# VDA.net
KiCad netlist of a schematic drawn in EAGLE
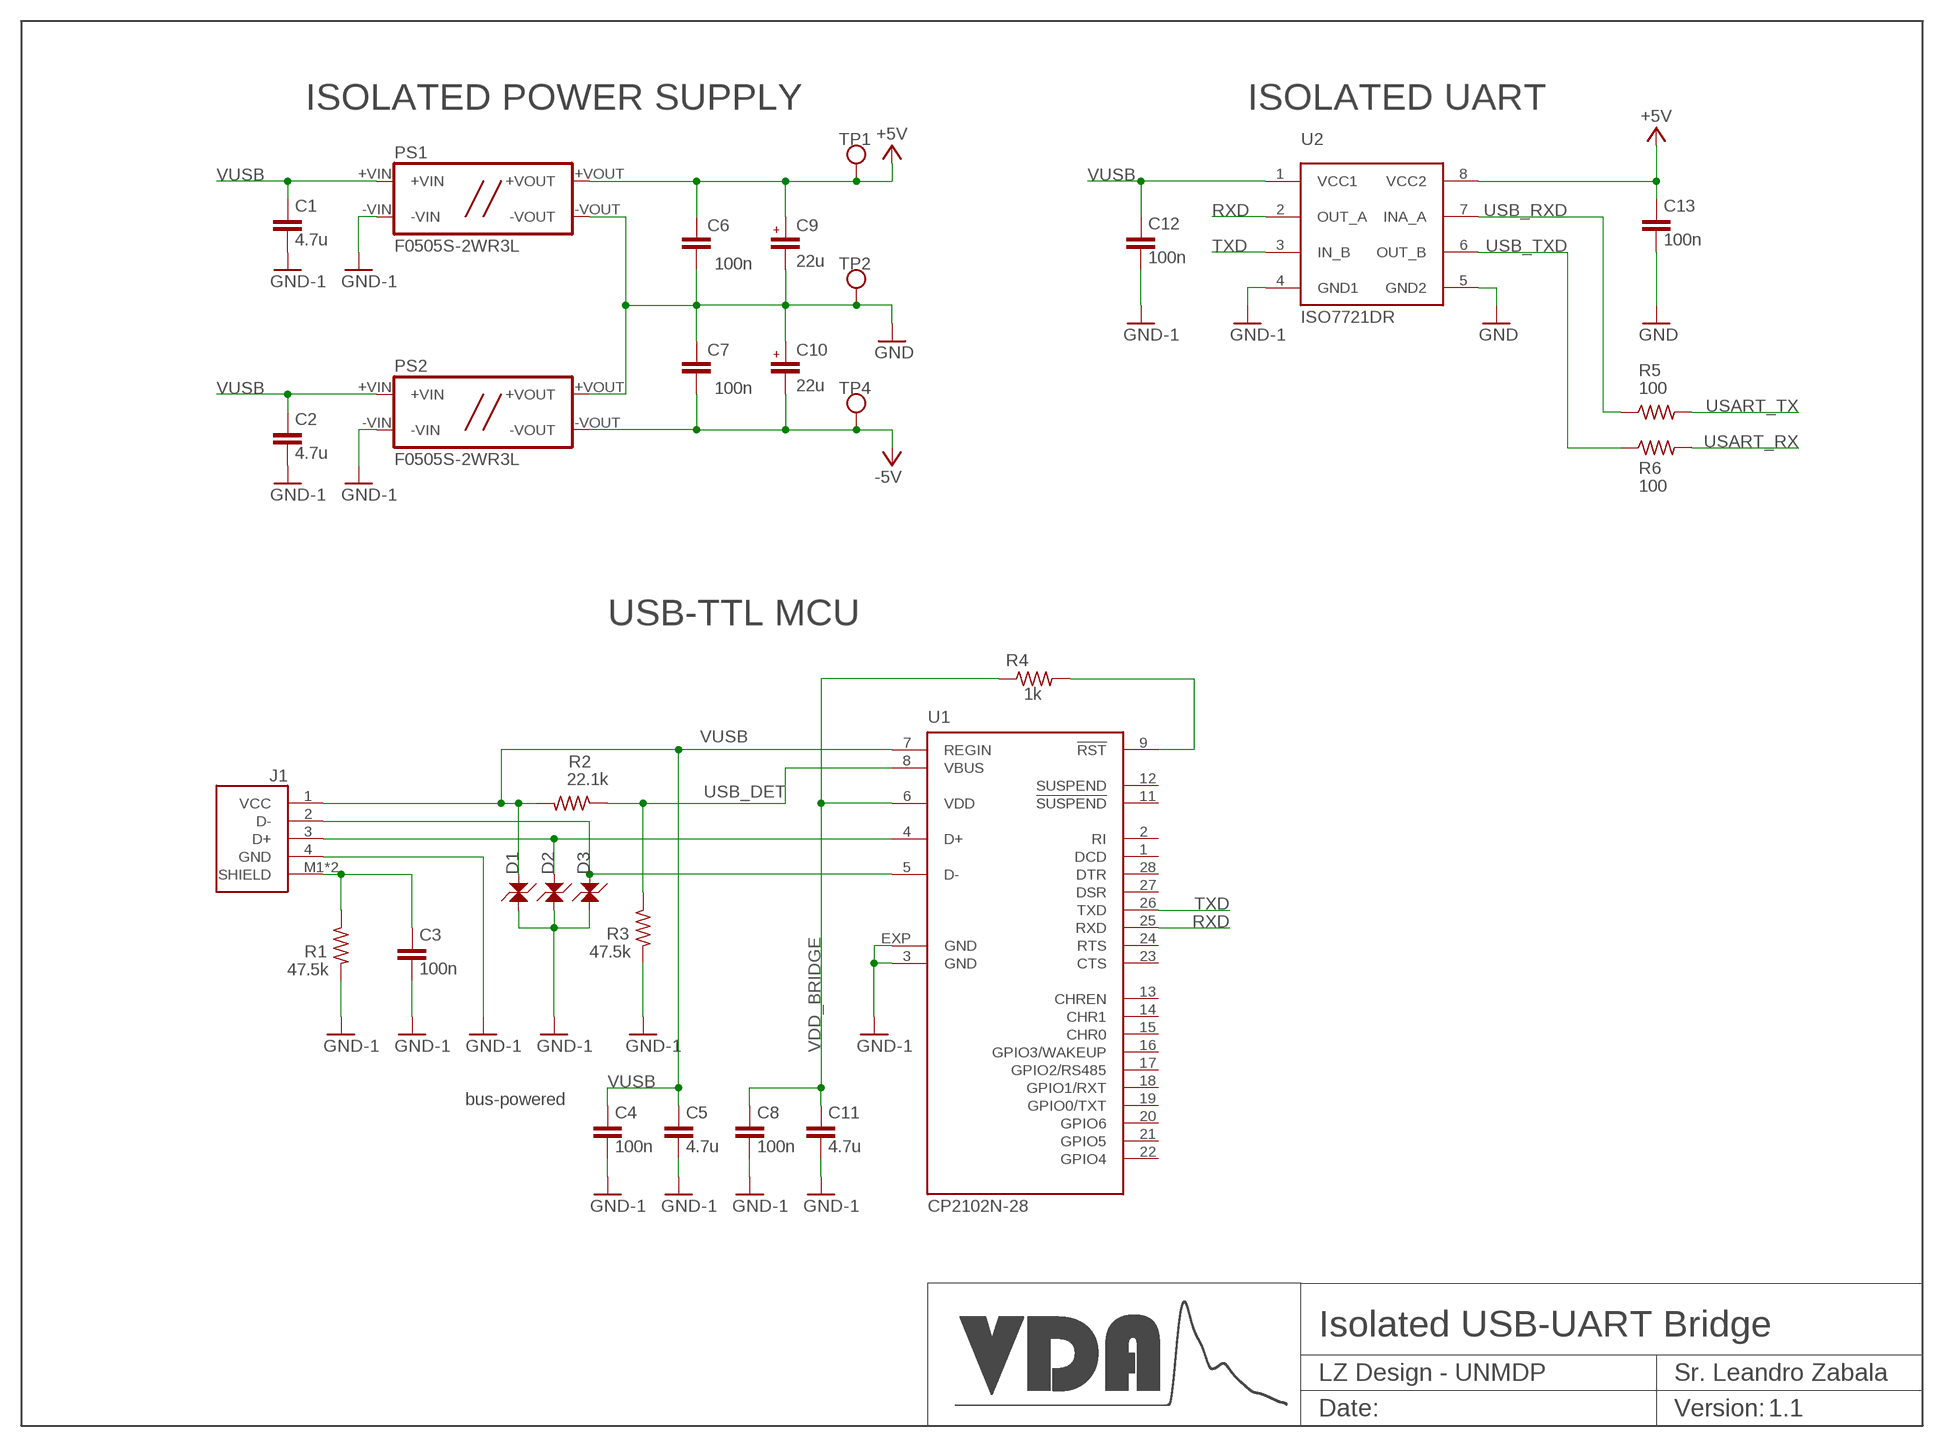
[diagram p0: schematic, sheet 1]
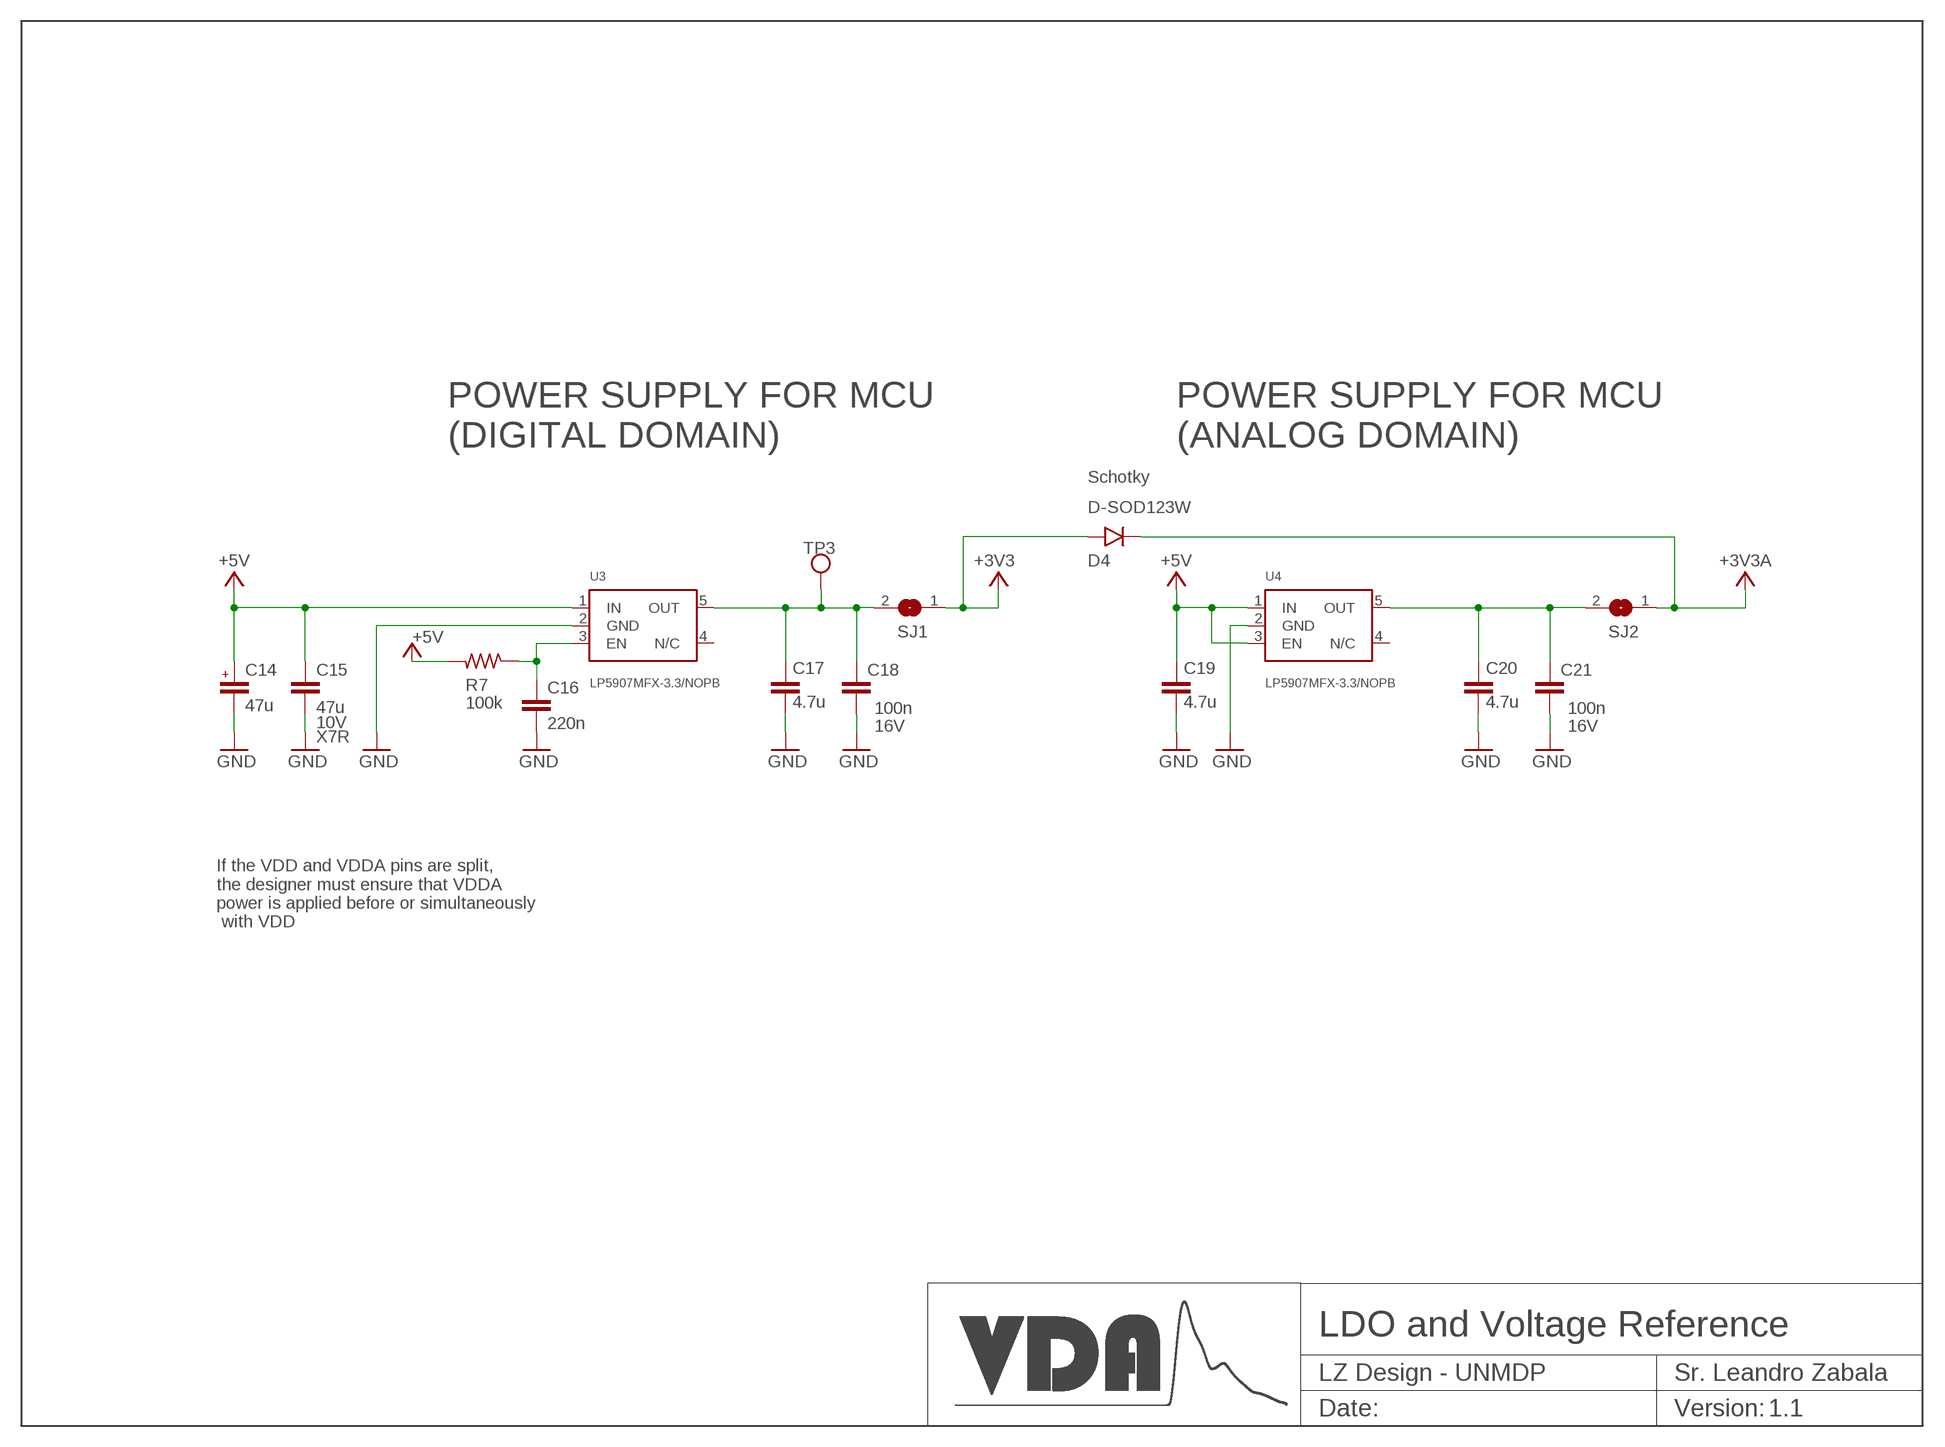
[diagram p1: schematic, sheet 2]
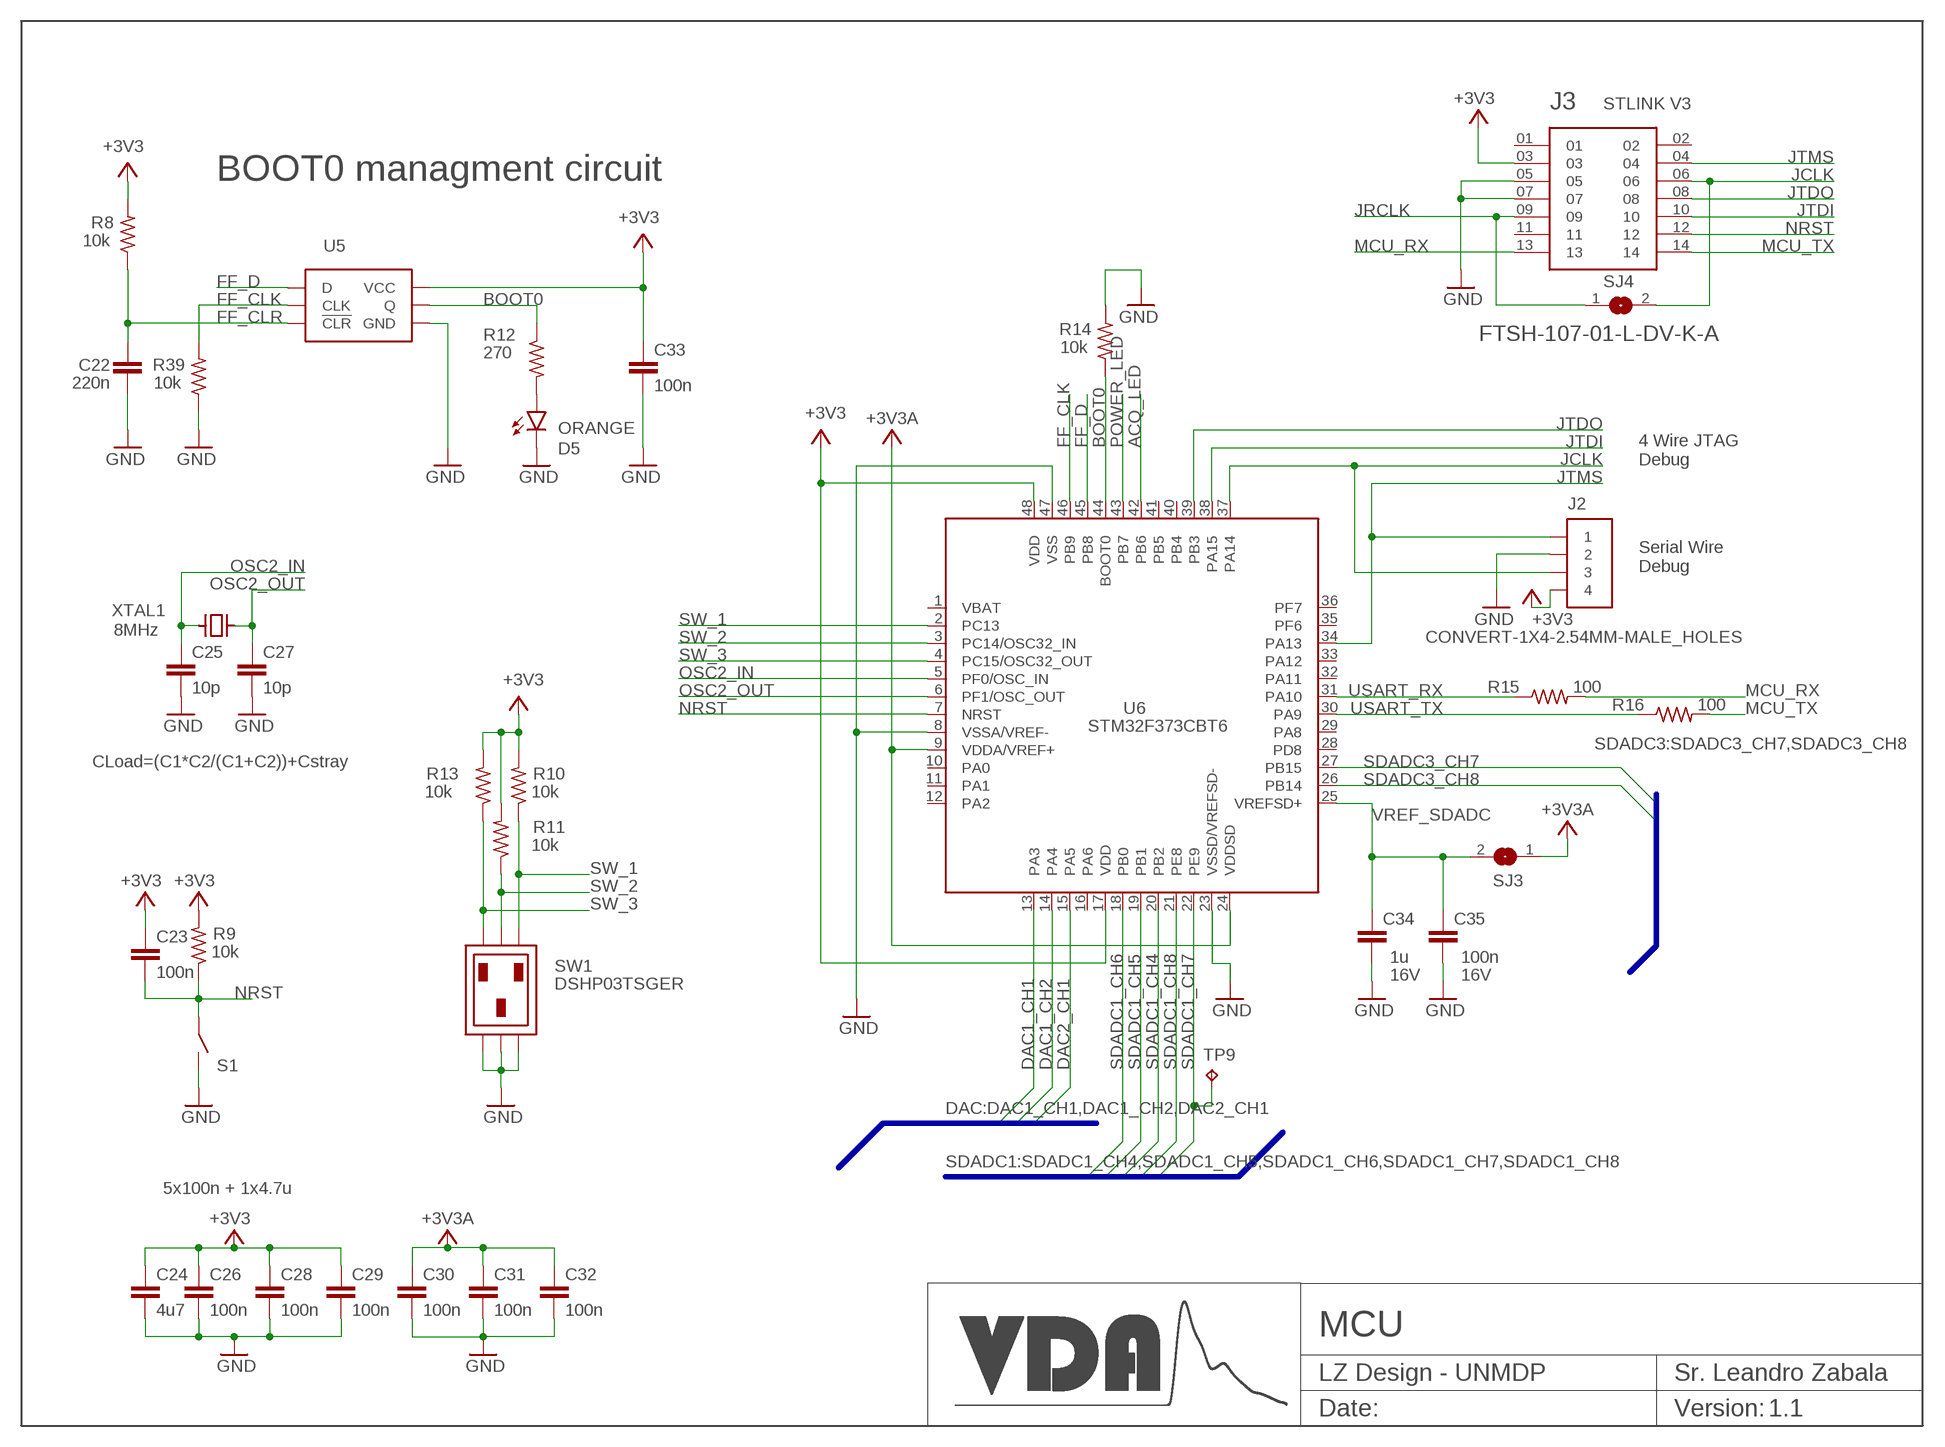
[diagram p2: schematic, sheet 3]
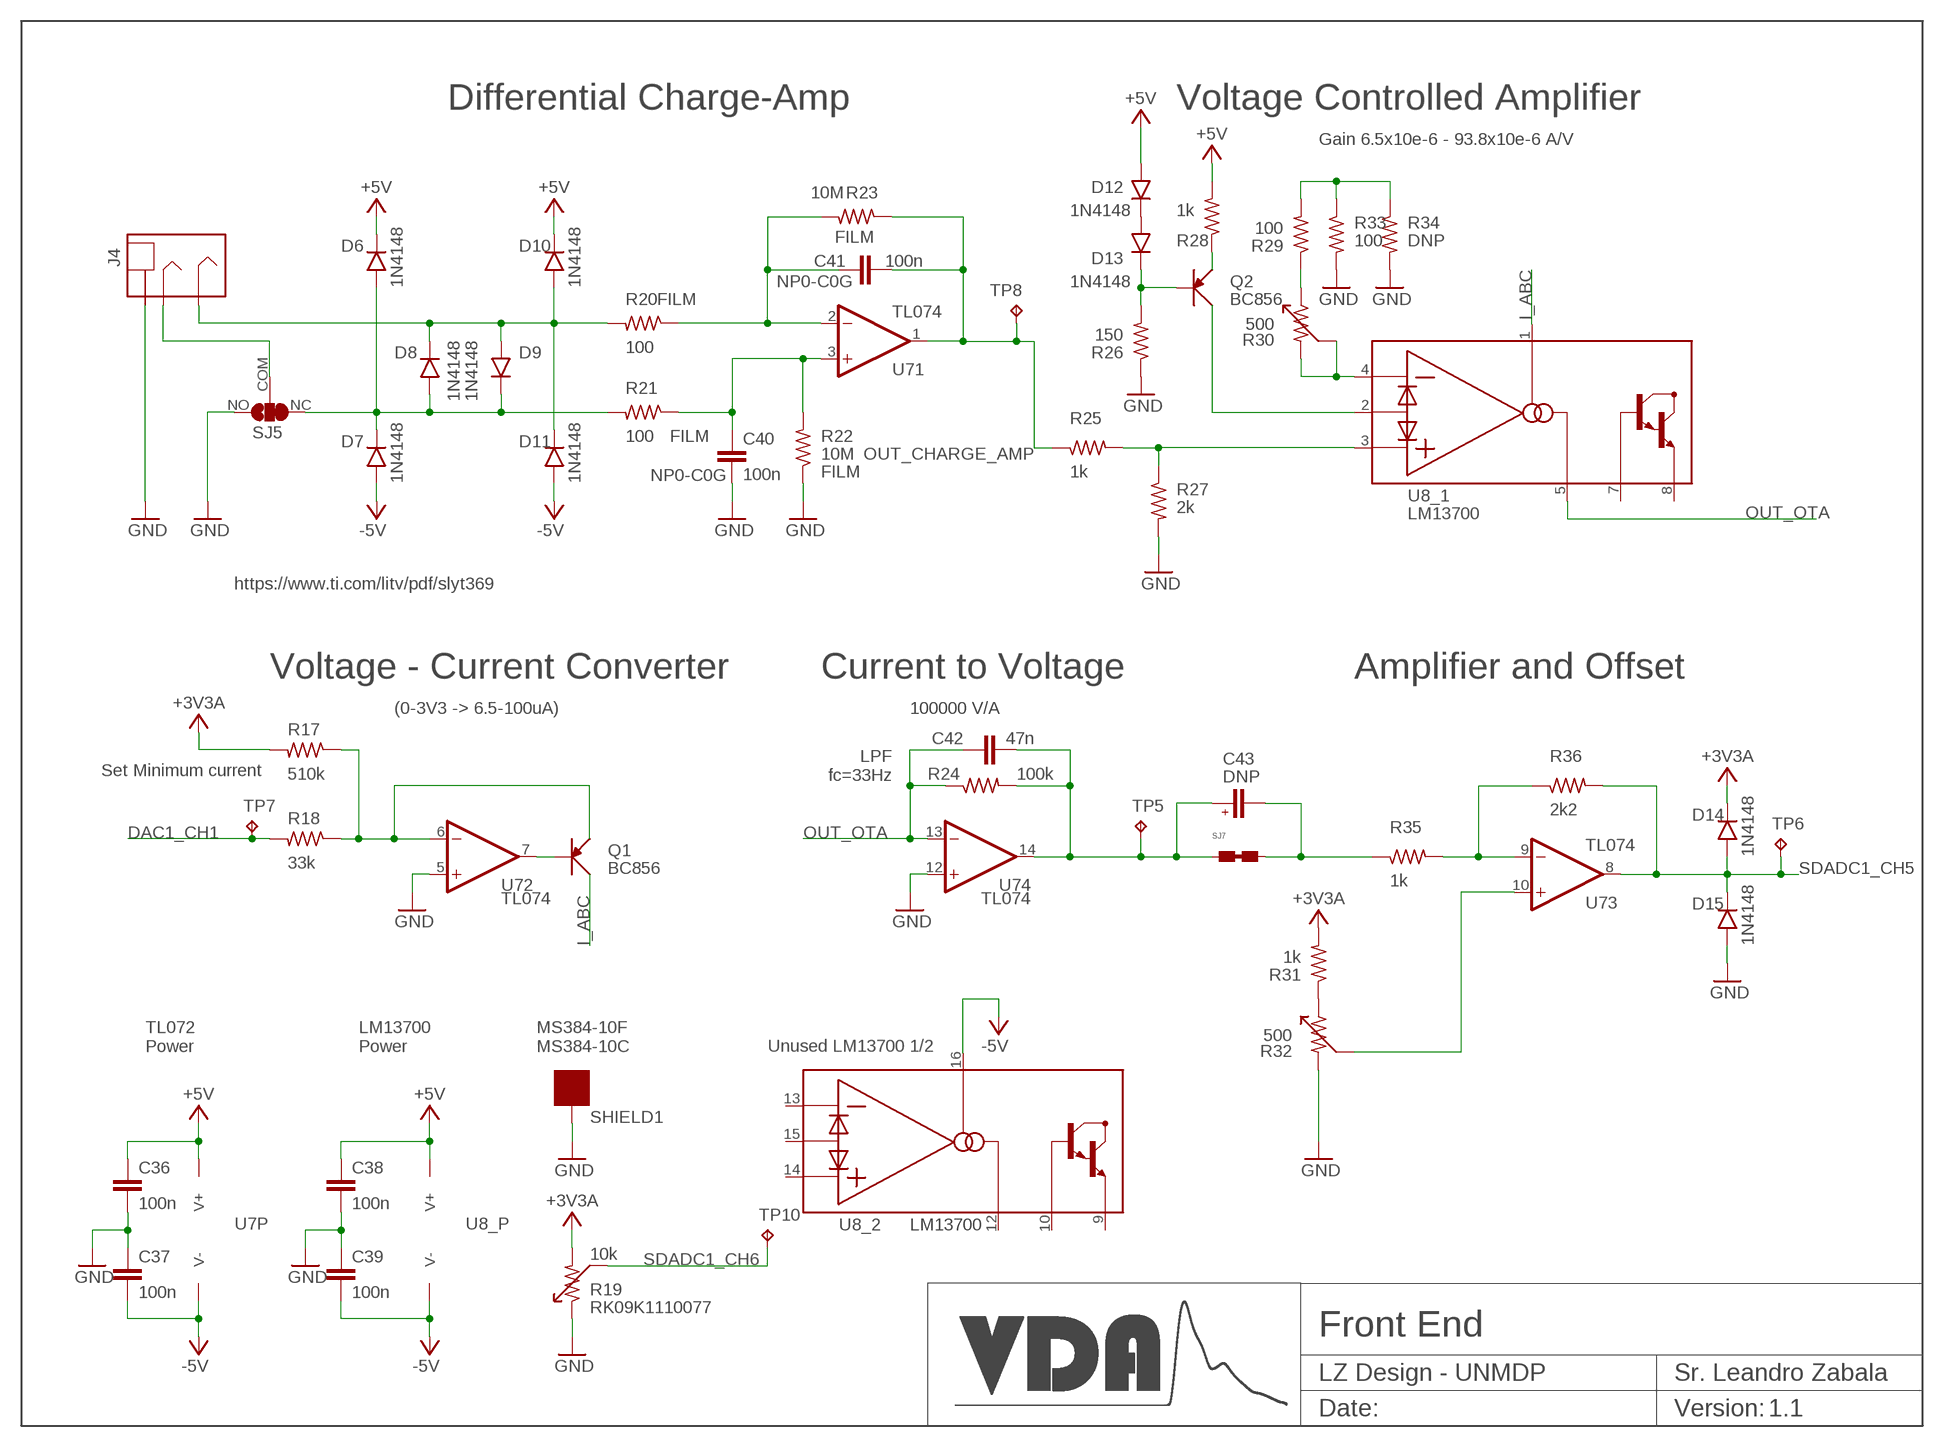
[diagram p3: schematic, sheet 4]
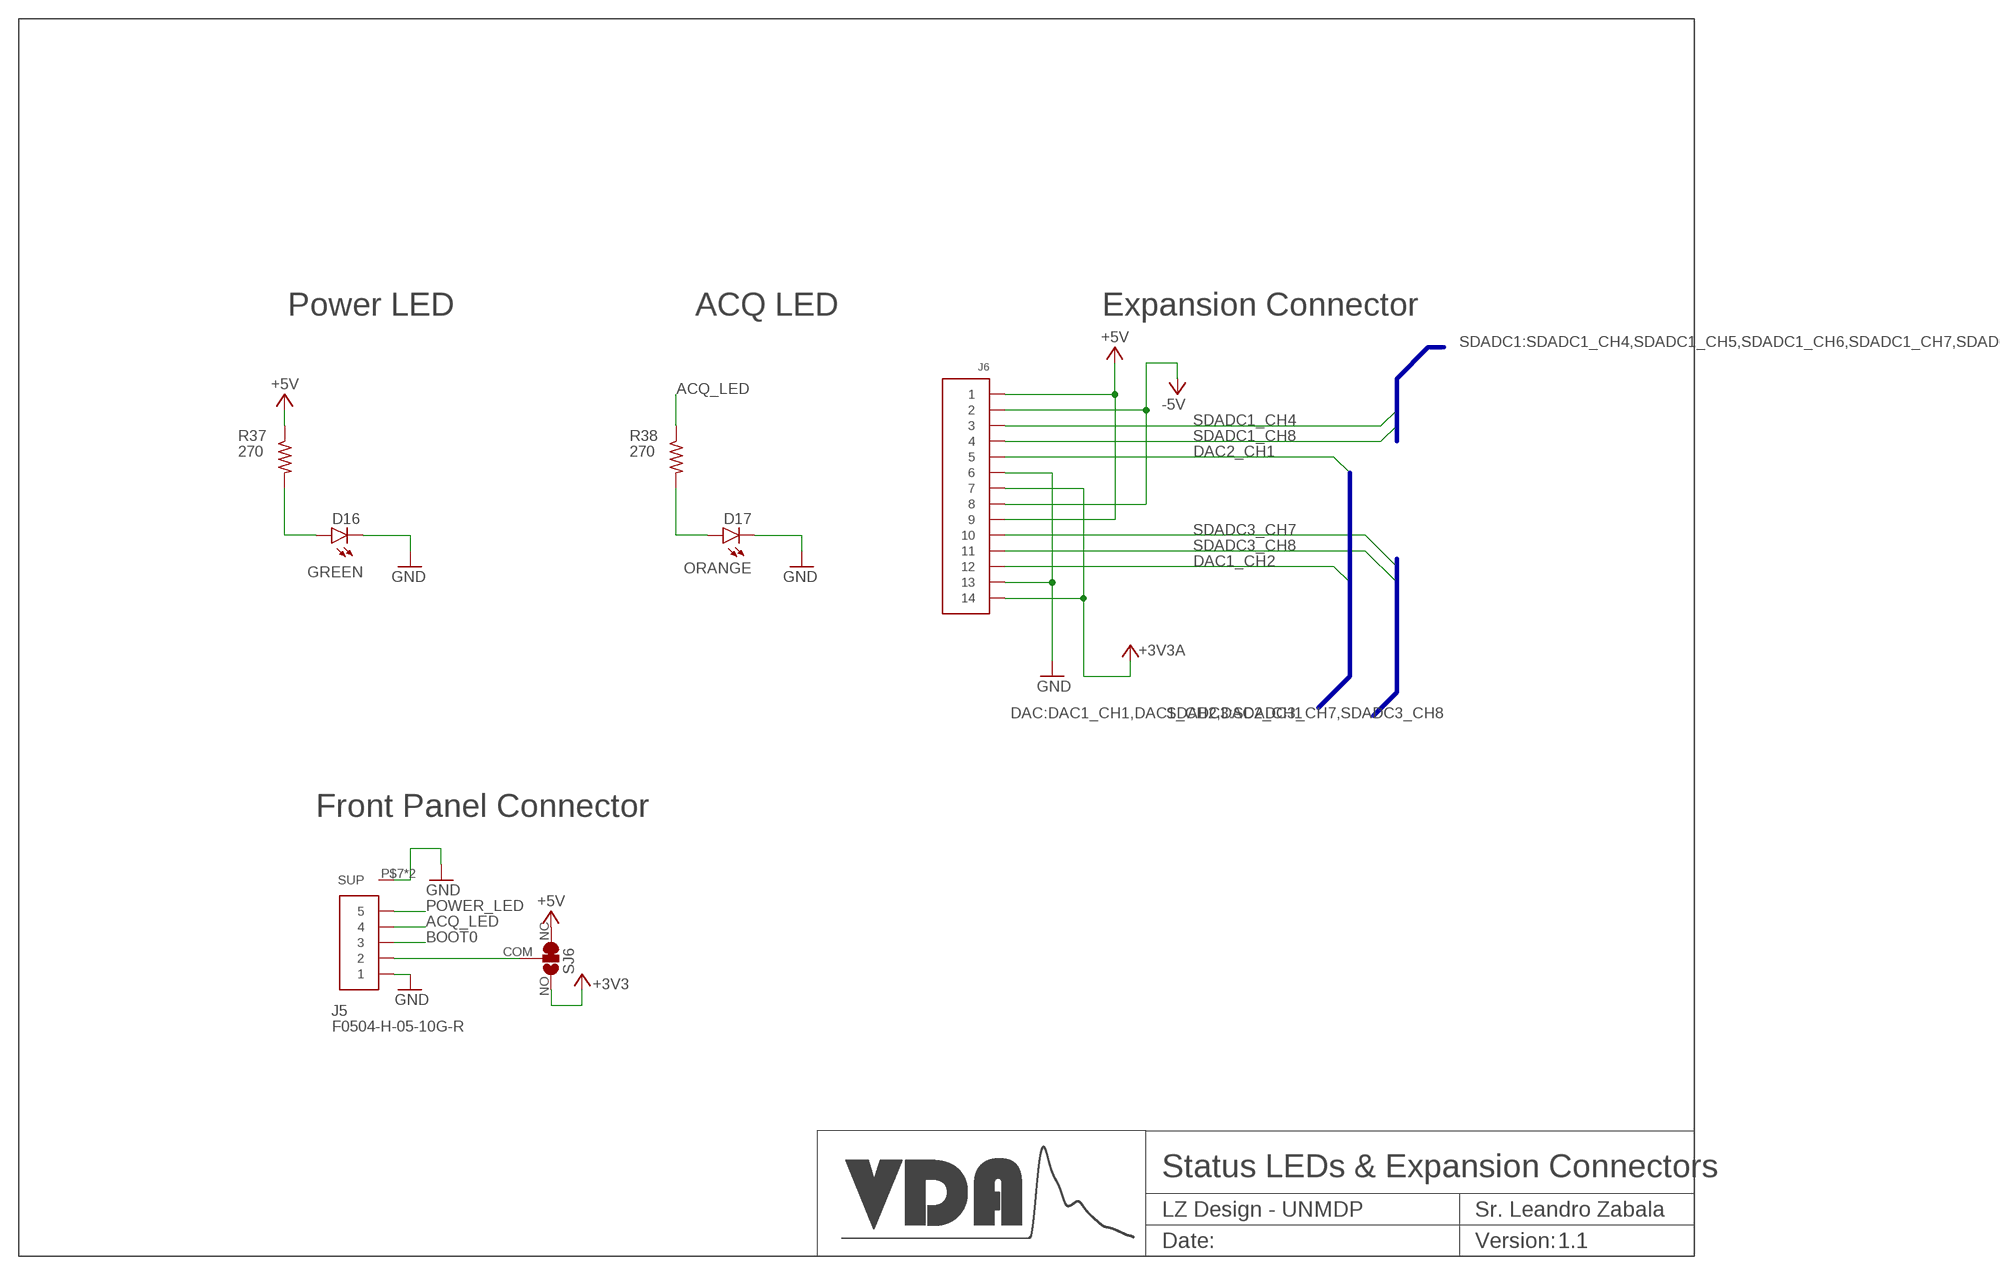
[diagram p4: schematic, sheet 5]

(export (version "E")
  (design (tool "Eeschema 10.0.6"))
  (components
    (comp (ref "C22")
      (value "220n")
      (footprint "eagle-import:C_0603")
      (libsource (lib "eagle-import") (part "C_0603"))
    )
    (comp (ref "C23")
      (value "100n")
      (footprint "eagle-import:C_0603")
      (libsource (lib "eagle-import") (part "C_0603"))
    )
    (comp (ref "C24")
      (value "4u7")
      (footprint "eagle-import:C_0805")
      (libsource (lib "eagle-import") (part "C_0805"))
    )
    (comp (ref "C25")
      (value "10p")
      (footprint "eagle-import:C_0603")
      (libsource (lib "eagle-import") (part "C_0603"))
    )
    (comp (ref "C26")
      (value "100n")
      (footprint "eagle-import:C_0603")
      (libsource (lib "eagle-import") (part "C_0603"))
    )
    (comp (ref "C27")
      (value "10p")
      (footprint "eagle-import:C_0603")
      (libsource (lib "eagle-import") (part "C_0603"))
    )
    (comp (ref "C28")
      (value "100n")
      (footprint "eagle-import:C_0603")
      (libsource (lib "eagle-import") (part "C_0603"))
    )
    (comp (ref "C29")
      (value "100n")
      (footprint "eagle-import:C_0603")
      (libsource (lib "eagle-import") (part "C_0603"))
    )
    (comp (ref "C30")
      (value "100n")
      (footprint "eagle-import:C_0603")
      (libsource (lib "eagle-import") (part "C_0603"))
    )
    (comp (ref "C31")
      (value "100n")
      (footprint "eagle-import:C_0603")
      (libsource (lib "eagle-import") (part "C_0603"))
    )
    (comp (ref "C32")
      (value "100n")
      (footprint "eagle-import:C_0603")
      (libsource (lib "eagle-import") (part "C_0603"))
    )
    (comp (ref "C33")
      (value "100n")
      (footprint "eagle-import:C_0603")
      (libsource (lib "eagle-import") (part "C_0603"))
    )
    (comp (ref "C34")
      (value "1u")
      (footprint "eagle-import:C_0603")
      (fields (field (name "V") "16V"))
      (libsource (lib "eagle-import") (part "C_0603"))
    )
    (comp (ref "C35")
      (value "100n")
      (footprint "eagle-import:C_0603")
      (fields (field (name "V") "16V"))
      (libsource (lib "eagle-import") (part "C_0603"))
    )
    (comp (ref "D5")
      (value "ORANGE")
      (footprint "eagle-import:LED_0603_ARROW")
      (libsource (lib "eagle-import") (part "LED_0603_ARROW"))
    )
    (comp (ref "J2")
      (value "CONVERT-1X4-2.54MM-MALE_HOLES")
      (footprint "eagle-import:1X04")
      (libsource (lib "eagle-import") (part "CONVERT-1X4-2.54MM-MALE_HOLES"))
    )
    (comp (ref "J3")
      (value "FTSH-107-01-L-DV-K-A")
      (footprint "eagle-import:SAMTEC_FTSH-107-01-L-DV-K-A")
      (fields (field (name "MANUFACTURER") "Samtec"))
      (libsource (lib "eagle-import") (part "FTSH-107-01-L-DV-K-A"))
    )
    (comp (ref "R8")
      (value "10k")
      (footprint "eagle-import:R_0603")
      (libsource (lib "eagle-import") (part "R_0603"))
    )
    (comp (ref "R9")
      (value "10k")
      (footprint "eagle-import:R_0603")
      (libsource (lib "eagle-import") (part "R_0603"))
    )
    (comp (ref "R10")
      (value "10k")
      (footprint "eagle-import:R_0603")
      (libsource (lib "eagle-import") (part "R_0603"))
    )
    (comp (ref "R11")
      (value "10k")
      (footprint "eagle-import:R_0603")
      (libsource (lib "eagle-import") (part "R_0603"))
    )
    (comp (ref "R12")
      (value "270")
      (footprint "eagle-import:R_0603")
      (libsource (lib "eagle-import") (part "R_0603"))
    )
    (comp (ref "R13")
      (value "10k")
      (footprint "eagle-import:R_0603")
      (libsource (lib "eagle-import") (part "R_0603"))
    )
    (comp (ref "R14")
      (value "10k")
      (footprint "eagle-import:R_0603")
      (libsource (lib "eagle-import") (part "R_0603"))
    )
    (comp (ref "R15")
      (value "100")
      (footprint "eagle-import:R_0603")
      (libsource (lib "eagle-import") (part "R_0603"))
    )
    (comp (ref "R16")
      (value "100")
      (footprint "eagle-import:R_0603")
      (libsource (lib "eagle-import") (part "R_0603"))
    )
    (comp (ref "R39")
      (value "10k")
      (footprint "eagle-import:R_0603")
      (libsource (lib "eagle-import") (part "R_0603"))
    )
    (comp (ref "S1")
      (value "TSWITCH_SMTR2")
      (footprint "eagle-import:SMTR2")
      (libsource (lib "eagle-import") (part "TSWITCH_SMTR2"))
    )
    (comp (ref "SJ3") (value "SJ") (footprint "eagle-import:SJ") (libsource (lib "eagle-import") (part "SJ")))
    (comp (ref "SJ4") (value "SJ") (footprint "eagle-import:SJ") (libsource (lib "eagle-import") (part "SJ")))
    (comp (ref "SW1")
      (value "DSHP03TSGER")
      (footprint "eagle-import:DIPSW-3")
      (libsource (lib "eagle-import") (part "DIPSW-3"))
    )
    (comp (ref "TP9")
      (value "TPTP16R")
      (footprint "eagle-import:TP16R")
      (libsource (lib "eagle-import") (part "TPTP16R"))
    )
    (comp (ref "U5")
      (value "SN74LVC1G175")
      (footprint "eagle-import:SOT-23-6")
      (libsource (lib "eagle-import") (part "SN74LVC1G175"))
    )
    (comp (ref "U6")
      (value "STM32F373CBT6")
      (footprint "eagle-import:QFP50P900X900X160-48N")
      (libsource (lib "eagle-import") (part "STM32F373-48CT"))
    )
    (comp (ref "XTAL1")
      (value "8MHz")
      (footprint "eagle-import:XTAL3.2X2.5")
      (fields (field (name "MPN") "830108313809"))
      (libsource (lib "eagle-import") (part "XTAL3.2X2.5"))
    )
    (comp (ref "C14")
      (value "47u")
      (footprint "eagle-import:A_3216")
      (libsource (lib "eagle-import") (part "C-TANTALUM_A_3216"))
    )
    (comp (ref "C15")
      (value "47u")
      (footprint "eagle-import:C_1206")
      (fields (field (name "D") "X7R") (field (name "ESR") "LOW") (field (name "V") "10V"))
      (libsource (lib "eagle-import") (part "C_1206"))
    )
    (comp (ref "C16")
      (value "220n")
      (footprint "eagle-import:C_0603")
      (libsource (lib "eagle-import") (part "C_0603"))
    )
    (comp (ref "C17")
      (value "4.7u")
      (footprint "eagle-import:C_0805")
      (libsource (lib "eagle-import") (part "C_0805"))
    )
    (comp (ref "C18")
      (value "100n")
      (footprint "eagle-import:C_0603")
      (fields (field (name "V") "16V"))
      (libsource (lib "eagle-import") (part "C_0603"))
    )
    (comp (ref "C19")
      (value "4.7u")
      (footprint "eagle-import:C_0805")
      (libsource (lib "eagle-import") (part "C_0805"))
    )
    (comp (ref "C20")
      (value "4.7u")
      (footprint "eagle-import:C_0805")
      (libsource (lib "eagle-import") (part "C_0805"))
    )
    (comp (ref "C21")
      (value "100n")
      (footprint "eagle-import:C_0603")
      (fields (field (name "V") "16V"))
      (libsource (lib "eagle-import") (part "C_0603"))
    )
    (comp (ref "D4")
      (value "D-SOD123W")
      (footprint "eagle-import:SOD123W")
      (fields (field (name "TYPE") "Schotky"))
      (libsource (lib "eagle-import") (part "D-SOD123W"))
    )
    (comp (ref "R7")
      (value "100k")
      (footprint "eagle-import:R_0603")
      (libsource (lib "eagle-import") (part "R_0603"))
    )
    (comp (ref "SJ1") (value "SJ") (footprint "eagle-import:SJ") (libsource (lib "eagle-import") (part "SJ")))
    (comp (ref "SJ2") (value "SJ") (footprint "eagle-import:SJ") (libsource (lib "eagle-import") (part "SJ")))
    (comp (ref "TP3")
      (value "HOLE_0.8MM")
      (footprint "eagle-import:HOLE_0.8MM")
      (libsource (lib "eagle-import") (part "HOLE_0.8MM"))
    )
    (comp (ref "U3")
      (value "LP5907MFX-3.3/NOPB")
      (footprint "eagle-import:SOT23-5")
      (libsource (lib "eagle-import") (part "LDO1SOT23-5_1"))
    )
    (comp (ref "U4")
      (value "LP5907MFX-3.3/NOPB")
      (footprint "eagle-import:SOT23-5")
      (libsource (lib "eagle-import") (part "LDO1SOT23-5_1"))
    )
    (comp (ref "D16")
      (value "GREEN")
      (footprint "eagle-import:LED_0603_ARROW")
      (libsource (lib "eagle-import") (part "LED_0603_ARROW"))
    )
    (comp (ref "D17")
      (value "ORANGE")
      (footprint "eagle-import:LED_0603_ARROW")
      (libsource (lib "eagle-import") (part "LED_0603_ARROW"))
    )
    (comp (ref "J5")
      (value "F0504-H-05-10G-R")
      (footprint "eagle-import:F0504-H-05-10G-R")
      (libsource (lib "eagle-import") (part "F0504-H-05-10G-R"))
    )
    (comp (ref "J6")
      (value "CONVERT-2X7-2.54MM-FEMALE")
      (footprint "eagle-import:CONN-VERT-2.54MM-2X7-FEMALE")
      (libsource (lib "eagle-import") (part "CONVERT-2X7-2.54MM-FEMALE"))
    )
    (comp (ref "R37")
      (value "270")
      (footprint "eagle-import:R_0603")
      (libsource (lib "eagle-import") (part "R_0603"))
    )
    (comp (ref "R38")
      (value "270")
      (footprint "eagle-import:R_0603")
      (libsource (lib "eagle-import") (part "R_0603"))
    )
    (comp (ref "SJ6")
      (value "SJ-PSS")
      (footprint "eagle-import:SJ_2S")
      (libsource (lib "eagle-import") (part "SJ-PSS"))
    )
    (comp (ref "C1")
      (value "4.7u")
      (footprint "eagle-import:C_0805")
      (libsource (lib "eagle-import") (part "C_0805"))
    )
    (comp (ref "C2")
      (value "4.7u")
      (footprint "eagle-import:C_0805")
      (libsource (lib "eagle-import") (part "C_0805"))
    )
    (comp (ref "C3")
      (value "100n")
      (footprint "eagle-import:C_0603")
      (libsource (lib "eagle-import") (part "C_0603"))
    )
    (comp (ref "C4")
      (value "100n")
      (footprint "eagle-import:C_0603")
      (libsource (lib "eagle-import") (part "C_0603"))
    )
    (comp (ref "C5")
      (value "4.7u")
      (footprint "eagle-import:C_0805")
      (libsource (lib "eagle-import") (part "C_0805"))
    )
    (comp (ref "C6")
      (value "100n")
      (footprint "eagle-import:C_0603")
      (libsource (lib "eagle-import") (part "C_0603"))
    )
    (comp (ref "C7")
      (value "100n")
      (footprint "eagle-import:C_0603")
      (libsource (lib "eagle-import") (part "C_0603"))
    )
    (comp (ref "C8")
      (value "100n")
      (footprint "eagle-import:C_0603")
      (libsource (lib "eagle-import") (part "C_0603"))
    )
    (comp (ref "C9")
      (value "22u")
      (footprint "eagle-import:CAPAE660X590N")
      (libsource (lib "eagle-import") (part "C-ELECT-6.3X5.4"))
    )
    (comp (ref "C10")
      (value "22u")
      (footprint "eagle-import:CAPAE660X590N")
      (libsource (lib "eagle-import") (part "C-ELECT-6.3X5.4"))
    )
    (comp (ref "C11")
      (value "4.7u")
      (footprint "eagle-import:C_0805")
      (libsource (lib "eagle-import") (part "C_0805"))
    )
    (comp (ref "C12")
      (value "100n")
      (footprint "eagle-import:C_0603")
      (libsource (lib "eagle-import") (part "C_0603"))
    )
    (comp (ref "C13")
      (value "100n")
      (footprint "eagle-import:C_0603")
      (libsource (lib "eagle-import") (part "C_0603"))
    )
    (comp (ref "D1")
      (value "LESD5D5.0CT1G")
      (footprint "eagle-import:SOD523")
      (libsource (lib "eagle-import") (part "LESD5D5.0CT1G"))
    )
    (comp (ref "D2")
      (value "LESD5D5.0CT1G")
      (footprint "eagle-import:SOD523")
      (libsource (lib "eagle-import") (part "LESD5D5.0CT1G"))
    )
    (comp (ref "D3")
      (value "LESD5D5.0CT1G")
      (footprint "eagle-import:SOD523")
      (libsource (lib "eagle-import") (part "LESD5D5.0CT1G"))
    )
    (comp (ref "J1")
      (value "USB-2.0")
      (footprint "eagle-import:USB-B")
      (libsource (lib "eagle-import") (part "USB-2.0"))
    )
    (comp (ref "PS1")
      (value "F0505S-2WR3L")
      (footprint "eagle-import:0505S-2WR3")
      (libsource (lib "eagle-import") (part "ISOLATED_DCDC"))
    )
    (comp (ref "PS2")
      (value "F0505S-2WR3L")
      (footprint "eagle-import:0505S-2WR3")
      (libsource (lib "eagle-import") (part "ISOLATED_DCDC"))
    )
    (comp (ref "R1")
      (value "47.5k")
      (footprint "eagle-import:R0402")
      (libsource (lib "eagle-import") (part "R-US_R0402"))
    )
    (comp (ref "R2")
      (value "22.1k")
      (footprint "eagle-import:R0402")
      (libsource (lib "eagle-import") (part "R-US_R0402"))
    )
    (comp (ref "R3")
      (value "47.5k")
      (footprint "eagle-import:R0402")
      (libsource (lib "eagle-import") (part "R-US_R0402"))
    )
    (comp (ref "R4")
      (value "1k")
      (footprint "eagle-import:R0402")
      (libsource (lib "eagle-import") (part "R-US_R0402"))
    )
    (comp (ref "R5")
      (value "100")
      (footprint "eagle-import:R_0603")
      (libsource (lib "eagle-import") (part "R_0603"))
    )
    (comp (ref "R6")
      (value "100")
      (footprint "eagle-import:R_0603")
      (libsource (lib "eagle-import") (part "R_0603"))
    )
    (comp (ref "TP1")
      (value "HOLE_0.8MM")
      (footprint "eagle-import:HOLE_0.8MM")
      (libsource (lib "eagle-import") (part "HOLE_0.8MM"))
    )
    (comp (ref "TP2")
      (value "HOLE_0.8MM")
      (footprint "eagle-import:HOLE_0.8MM")
      (libsource (lib "eagle-import") (part "HOLE_0.8MM"))
    )
    (comp (ref "TP4")
      (value "HOLE_0.8MM")
      (footprint "eagle-import:HOLE_0.8MM")
      (libsource (lib "eagle-import") (part "HOLE_0.8MM"))
    )
    (comp (ref "U1")
      (value "CP2102N-28")
      (footprint "eagle-import:MLP28")
      (libsource (lib "eagle-import") (part "CP2102N-28"))
    )
    (comp (ref "U2")
      (value "ISO7721DR")
      (footprint "eagle-import:SO8")
      (libsource (lib "eagle-import") (part "ISO7721DR"))
    )
    (comp (ref "C36")
      (value "100n")
      (footprint "eagle-import:C_0603")
      (libsource (lib "eagle-import") (part "C_0603"))
    )
    (comp (ref "C37")
      (value "100n")
      (footprint "eagle-import:C_0603")
      (libsource (lib "eagle-import") (part "C_0603"))
    )
    (comp (ref "C38")
      (value "100n")
      (footprint "eagle-import:C_0603")
      (libsource (lib "eagle-import") (part "C_0603"))
    )
    (comp (ref "C39")
      (value "100n")
      (footprint "eagle-import:C_0603")
      (libsource (lib "eagle-import") (part "C_0603"))
    )
    (comp (ref "C40")
      (value "100n")
      (footprint "eagle-import:C_1206")
      (description "NP0-C0G")
      (libsource (lib "eagle-import") (part "C_1206"))
    )
    (comp (ref "C41")
      (value "100n")
      (footprint "eagle-import:C_1206")
      (description "NP0-C0G")
      (libsource (lib "eagle-import") (part "C_1206"))
    )
    (comp (ref "C42")
      (value "47n")
      (footprint "eagle-import:C_0603")
      (libsource (lib "eagle-import") (part "C_0603"))
    )
    (comp (ref "C43")
      (value "DNP")
      (footprint "eagle-import:CAPAE830X680N")
      (libsource (lib "eagle-import") (part "C-ELECT_D8L6.5"))
    )
    (comp (ref "D6")
      (value "1N4148")
      (footprint "eagle-import:SOD123W")
      (libsource (lib "eagle-import") (part "D-SOD123W"))
    )
    (comp (ref "D7")
      (value "1N4148")
      (footprint "eagle-import:SOD123W")
      (libsource (lib "eagle-import") (part "D-SOD123W"))
    )
    (comp (ref "D8")
      (value "1N4148")
      (footprint "eagle-import:SOD123W")
      (libsource (lib "eagle-import") (part "D-SOD123W"))
    )
    (comp (ref "D9")
      (value "1N4148")
      (footprint "eagle-import:SOD123W")
      (libsource (lib "eagle-import") (part "D-SOD123W"))
    )
    (comp (ref "D10")
      (value "1N4148")
      (footprint "eagle-import:SOD123W")
      (libsource (lib "eagle-import") (part "D-SOD123W"))
    )
    (comp (ref "D11")
      (value "1N4148")
      (footprint "eagle-import:SOD123W")
      (libsource (lib "eagle-import") (part "D-SOD123W"))
    )
    (comp (ref "D12")
      (value "1N4148")
      (footprint "eagle-import:SOD123W")
      (libsource (lib "eagle-import") (part "D-SOD123W"))
    )
    (comp (ref "D13")
      (value "1N4148")
      (footprint "eagle-import:SOD123W")
      (libsource (lib "eagle-import") (part "D-SOD123W"))
    )
    (comp (ref "D14")
      (value "1N4148")
      (footprint "eagle-import:SOD123W")
      (libsource (lib "eagle-import") (part "D-SOD123W"))
    )
    (comp (ref "D15")
      (value "1N4148")
      (footprint "eagle-import:SOD123W")
      (libsource (lib "eagle-import") (part "D-SOD123W"))
    )
    (comp (ref "J4")
      (value "STEREO-JACK")
      (footprint "eagle-import:PJ-3200")
      (libsource (lib "eagle-import") (part "STEREO-JACK"))
    )
    (comp (ref "Q1")
      (value "BC856")
      (footprint "eagle-import:SOT-23")
      (libsource (lib "eagle-import") (part "PNP_SOT23"))
    )
    (comp (ref "Q2")
      (value "BC856")
      (footprint "eagle-import:SOT-23")
      (libsource (lib "eagle-import") (part "PNP_SOT23"))
    )
    (comp (ref "R17")
      (value "510k")
      (footprint "eagle-import:R_0603")
      (libsource (lib "eagle-import") (part "R_0603"))
    )
    (comp (ref "R18")
      (value "33k")
      (footprint "eagle-import:R_0603")
      (libsource (lib "eagle-import") (part "R_0603"))
    )
    (comp (ref "R19")
      (value "10k")
      (footprint "eagle-import:POT-09VR1M")
      (fields (field (name "MPN") "RK09K1110077"))
      (libsource (lib "eagle-import") (part "R-VARIABLE09VR1B"))
    )
    (comp (ref "R20")
      (value "100")
      (footprint "eagle-import:R_0603")
      (description "FILM")
      (libsource (lib "eagle-import") (part "R_0603"))
    )
    (comp (ref "R21")
      (value "100")
      (footprint "eagle-import:R_0603")
      (description "FILM")
      (libsource (lib "eagle-import") (part "R_0603"))
    )
    (comp (ref "R22")
      (value "10M")
      (footprint "eagle-import:R_0603")
      (description "FILM")
      (libsource (lib "eagle-import") (part "R_0603"))
    )
    (comp (ref "R23")
      (value "10M")
      (footprint "eagle-import:R_0603")
      (description "FILM")
      (libsource (lib "eagle-import") (part "R_0603"))
    )
    (comp (ref "R24")
      (value "100k")
      (footprint "eagle-import:R_0603")
      (libsource (lib "eagle-import") (part "R_0603"))
    )
    (comp (ref "R25")
      (value "1k")
      (footprint "eagle-import:R_0603")
      (libsource (lib "eagle-import") (part "R_0603"))
    )
    (comp (ref "R26")
      (value "150")
      (footprint "eagle-import:R_0603")
      (libsource (lib "eagle-import") (part "R_0603"))
    )
    (comp (ref "R27")
      (value "2k")
      (footprint "eagle-import:R_0603")
      (libsource (lib "eagle-import") (part "R_0603"))
    )
    (comp (ref "R28")
      (value "1k")
      (footprint "eagle-import:R_0603")
      (libsource (lib "eagle-import") (part "R_0603"))
    )
    (comp (ref "R29")
      (value "100")
      (footprint "eagle-import:R_0603")
      (libsource (lib "eagle-import") (part "R_0603"))
    )
    (comp (ref "R30")
      (value "500")
      (footprint "eagle-import:RV3.2X4")
      (fields (field (name "MPN") "3224W-1-501E"))
      (libsource (lib "eagle-import") (part "R-VARIABLE-3.2X4"))
    )
    (comp (ref "R31")
      (value "1k")
      (footprint "eagle-import:R_0603")
      (libsource (lib "eagle-import") (part "R_0603"))
    )
    (comp (ref "R32")
      (value "500")
      (footprint "eagle-import:RV3.2X4")
      (fields (field (name "MPN") "3224W-1-501E"))
      (libsource (lib "eagle-import") (part "R-VARIABLE-3.2X4"))
    )
    (comp (ref "R33")
      (value "100")
      (footprint "eagle-import:R_0603")
      (libsource (lib "eagle-import") (part "R_0603"))
    )
    (comp (ref "R34")
      (value "DNP")
      (footprint "eagle-import:R_0603")
      (libsource (lib "eagle-import") (part "R_0603"))
    )
    (comp (ref "R35")
      (value "1k")
      (footprint "eagle-import:R_0603")
      (libsource (lib "eagle-import") (part "R_0603"))
    )
    (comp (ref "R36")
      (value "2k2")
      (footprint "eagle-import:R_0603")
      (libsource (lib "eagle-import") (part "R_0603"))
    )
    (comp (ref "SHIELD1")
      (value "MS384")
      (footprint "eagle-import:MS384")
      (libsource (lib "eagle-import") (part "MS384"))
    )
    (comp (ref "SJ5")
      (value "SJ-PSS")
      (footprint "eagle-import:SJ_2S")
      (libsource (lib "eagle-import") (part "SJ-PSS"))
    )
    (comp (ref "SJ7")
      (value "SJUMPER-NC")
      (footprint "eagle-import:SJ1")
      (libsource (lib "eagle-import") (part "SJUMPER-NC"))
    )
    (comp (ref "TP5")
      (value "TPTP16R")
      (footprint "eagle-import:TP16R")
      (libsource (lib "eagle-import") (part "TPTP16R"))
    )
    (comp (ref "TP6")
      (value "TPTP16R")
      (footprint "eagle-import:TP16R")
      (libsource (lib "eagle-import") (part "TPTP16R"))
    )
    (comp (ref "TP7")
      (value "TPTP16R")
      (footprint "eagle-import:TP16R")
      (libsource (lib "eagle-import") (part "TPTP16R"))
    )
    (comp (ref "TP8")
      (value "TPTP16R")
      (footprint "eagle-import:TP16R")
      (libsource (lib "eagle-import") (part "TPTP16R"))
    )
    (comp (ref "TP10")
      (value "TPTP16R")
      (footprint "eagle-import:TP16R")
      (libsource (lib "eagle-import") (part "TPTP16R"))
    )
    (comp (ref "U7")
      (value "TL074")
      (footprint "eagle-import:SOIC127P600X175-14N")
      (libsource (lib "eagle-import") (part "LM324BD"))
    )
    (comp (ref "U8")
      (value "LM13700")
      (footprint "eagle-import:SO16")
      (libsource (lib "eagle-import") (part "LM13700"))
    )
  )
  (nets
    (net (code "10") (name "+3V3") (class "Default")
      (node (ref "C23") (pin "P$1") (pinfunction "1_P$1") (pintype "passive"))
      (node (ref "C24") (pin "P$1") (pinfunction "1_P$1") (pintype "passive"))
      (node (ref "C26") (pin "P$1") (pinfunction "1_P$1") (pintype "passive"))
      (node (ref "C28") (pin "P$1") (pinfunction "1_P$1") (pintype "passive"))
      (node (ref "C29") (pin "P$1") (pinfunction "1_P$1") (pintype "passive"))
      (node (ref "C33") (pin "P$1") (pinfunction "1_P$1") (pintype "passive"))
      (node (ref "D4") (pin "A") (pinfunction "A_A") (pintype "bidirectional"))
      (node (ref "J2") (pin "4") (pinfunction "4_4") (pintype "bidirectional"))
      (node (ref "J3") (pin "03") (pinfunction "03_03") (pintype "passive"))
      (node (ref "R10") (pin "2") (pinfunction "2_2") (pintype "passive"))
      (node (ref "R11") (pin "2") (pinfunction "2_2") (pintype "passive"))
      (node (ref "R13") (pin "2") (pinfunction "2_2") (pintype "passive"))
      (node (ref "R8") (pin "2") (pinfunction "2_2") (pintype "passive"))
      (node (ref "R9") (pin "2") (pinfunction "2_2") (pintype "passive"))
      (node (ref "SJ1") (pin "1") (pinfunction "1_1") (pintype "passive"))
      (node (ref "SJ6") (pin "NO") (pinfunction "NO_NO") (pintype "passive"))
      (node (ref "U5") (pin "5") (pinfunction "VCC_5") (pintype "power_in"))
      (node (ref "U6") (pin "17") (pinfunction "VDD_17") (pintype "power_in"))
      (node (ref "U6") (pin "48") (pinfunction "VDD_48") (pintype "power_in"))
    )
    (net (code "11") (name "+3V3A") (class "Default")
      (node (ref "C30") (pin "P$1") (pinfunction "1_P$1") (pintype "passive"))
      (node (ref "C31") (pin "P$1") (pinfunction "1_P$1") (pintype "passive"))
      (node (ref "C32") (pin "P$1") (pinfunction "1_P$1") (pintype "passive"))
      (node (ref "D14") (pin "C") (pinfunction "K_C") (pintype "bidirectional"))
      (node (ref "D4") (pin "C") (pinfunction "K_C") (pintype "bidirectional"))
      (node (ref "J6") (pin "14") (pinfunction "14_14") (pintype "bidirectional"))
      (node (ref "J6") (pin "7") (pinfunction "7_7") (pintype "bidirectional"))
      (node (ref "R17") (pin "2") (pinfunction "2_2") (pintype "passive"))
      (node (ref "R19") (pin "P$3") (pinfunction "2_P$3") (pintype "passive"))
      (node (ref "R31") (pin "2") (pinfunction "2_2") (pintype "passive"))
      (node (ref "SJ2") (pin "1") (pinfunction "1_1") (pintype "passive"))
      (node (ref "SJ3") (pin "1") (pinfunction "1_1") (pintype "passive"))
      (node (ref "U6") (pin "24") (pinfunction "VDDSD_24") (pintype "power_in"))
      (node (ref "U6") (pin "9") (pinfunction "VDDA/VREF+_9") (pintype "input"))
    )
    (net (code "12") (name "+5V") (class "Default")
      (node (ref "C13") (pin "P$1") (pinfunction "1_P$1") (pintype "passive"))
      (node (ref "C14") (pin "A") (pinfunction "+_A") (pintype "passive"))
      (node (ref "C15") (pin "P$1") (pinfunction "1_P$1") (pintype "passive"))
      (node (ref "C19") (pin "P$1") (pinfunction "1_P$1") (pintype "passive"))
      (node (ref "C36") (pin "P$1") (pinfunction "1_P$1") (pintype "passive"))
      (node (ref "C38") (pin "P$1") (pinfunction "1_P$1") (pintype "passive"))
      (node (ref "C6") (pin "P$1") (pinfunction "1_P$1") (pintype "passive"))
      (node (ref "C9") (pin "+") (pinfunction "+_+") (pintype "passive"))
      (node (ref "D10") (pin "C") (pinfunction "K_C") (pintype "bidirectional"))
      (node (ref "D12") (pin "A") (pinfunction "A_A") (pintype "bidirectional"))
      (node (ref "D6") (pin "C") (pinfunction "K_C") (pintype "bidirectional"))
      (node (ref "J6") (pin "1") (pinfunction "1_1") (pintype "bidirectional"))
      (node (ref "J6") (pin "9") (pinfunction "9_9") (pintype "bidirectional"))
      (node (ref "PS1") (pin "+VOUT") (pinfunction "+VOUT_+VOUT") (pintype "passive"))
      (node (ref "R28") (pin "2") (pinfunction "2_2") (pintype "passive"))
      (node (ref "R37") (pin "1") (pinfunction "1_1") (pintype "passive"))
      (node (ref "R7") (pin "2") (pinfunction "2_2") (pintype "passive"))
      (node (ref "SJ6") (pin "NC") (pinfunction "NC_NC") (pintype "passive"))
      (node (ref "TP1") (pin "1") (pinfunction "P_1") (pintype "bidirectional"))
      (node (ref "U2") (pin "8") (pinfunction "VCC2_8") (pintype "power_in"))
      (node (ref "U3") (pin "1") (pinfunction "IN_1") (pintype "power_in"))
      (node (ref "U4") (pin "1") (pinfunction "IN_1") (pintype "power_in"))
      (node (ref "U4") (pin "3") (pinfunction "EN_3") (pintype "input"))
      (node (ref "U7") (pin "4") (pinfunction "V+_4") (pintype "power_in"))
      (node (ref "U8") (pin "11") (pinfunction "V+_11") (pintype "power_in"))
    )
    (net (code "13") (name "-5V") (class "Default")
      (node (ref "C10") (pin "-") (pinfunction "-_-") (pintype "passive"))
      (node (ref "C37") (pin "P$2") (pinfunction "2_P$2") (pintype "passive"))
      (node (ref "C39") (pin "P$2") (pinfunction "2_P$2") (pintype "passive"))
      (node (ref "C7") (pin "P$2") (pinfunction "2_P$2") (pintype "passive"))
      (node (ref "D11") (pin "A") (pinfunction "A_A") (pintype "bidirectional"))
      (node (ref "D7") (pin "A") (pinfunction "A_A") (pintype "bidirectional"))
      (node (ref "J6") (pin "2") (pinfunction "2_2") (pintype "bidirectional"))
      (node (ref "J6") (pin "8") (pinfunction "8_8") (pintype "bidirectional"))
      (node (ref "PS2") (pin "-VOUT") (pinfunction "-VOUT_-VOUT") (pintype "passive"))
      (node (ref "TP4") (pin "1") (pinfunction "P_1") (pintype "bidirectional"))
      (node (ref "U7") (pin "11") (pinfunction "V-_11") (pintype "power_in"))
      (node (ref "U8") (pin "16") (pinfunction "AMP_BIAS_16") (pintype "bidirectional"))
      (node (ref "U8") (pin "6") (pinfunction "V-_6") (pintype "power_in"))
    )
    (net (code "20") (name "ACQ_LED") (class "Default")
      (node (ref "J5") (pin "P$4") (pinfunction "4_P$4") (pintype "bidirectional"))
      (node (ref "R38") (pin "1") (pinfunction "1_1") (pintype "passive"))
      (node (ref "U6") (pin "42") (pinfunction "PB6_42") (pintype "bidirectional"))
    )
    (net (code "21") (name "BOOT0") (class "Default")
      (node (ref "J5") (pin "P$3") (pinfunction "3_P$3") (pintype "bidirectional"))
      (node (ref "R12") (pin "1") (pinfunction "1_1") (pintype "passive"))
      (node (ref "R14") (pin "1") (pinfunction "1_1") (pintype "passive"))
      (node (ref "U5") (pin "4") (pinfunction "Q_4") (pintype "output"))
      (node (ref "U6") (pin "44") (pinfunction "BOOT0_44") (pintype "bidirectional"))
    )
    (net (code "22") (name "DAC1_CH1") (class "Default")
      (node (ref "R18") (pin "2") (pinfunction "2_2") (pintype "passive"))
      (node (ref "TP7") (pin "TP") (pinfunction "TP_TP") (pintype "input"))
      (node (ref "U6") (pin "13") (pinfunction "PA3_13") (pintype "bidirectional"))
    )
    (net (code "23") (name "DAC1_CH2") (class "Default")
      (node (ref "J6") (pin "12") (pinfunction "12_12") (pintype "bidirectional"))
      (node (ref "U6") (pin "14") (pinfunction "PA4_14") (pintype "bidirectional"))
    )
    (net (code "24") (name "DAC2_CH1") (class "Default")
      (node (ref "J6") (pin "5") (pinfunction "5_5") (pintype "bidirectional"))
      (node (ref "U6") (pin "15") (pinfunction "PA5_15") (pintype "bidirectional"))
    )
    (net (code "25") (name "FF_CLK") (class "Default")
      (node (ref "R39") (pin "2") (pinfunction "2_2") (pintype "passive"))
      (node (ref "U5") (pin "1") (pinfunction "CLK_1") (pintype "input"))
      (node (ref "U6") (pin "46") (pinfunction "PB9_46") (pintype "bidirectional"))
    )
    (net (code "26") (name "FF_CLR") (class "Default")
      (node (ref "C22") (pin "P$1") (pinfunction "1_P$1") (pintype "passive"))
      (node (ref "R8") (pin "1") (pinfunction "1_1") (pintype "passive"))
      (node (ref "U5") (pin "6") (pinfunction "~{CLR}_6") (pintype "input"))
    )
    (net (code "27") (name "FF_D") (class "Default")
      (node (ref "U5") (pin "3") (pinfunction "D_3") (pintype "input"))
      (node (ref "U6") (pin "45") (pinfunction "PB8_45") (pintype "bidirectional"))
    )
    (net (code "28") (name "GND") (class "Default")
      (node (ref "C10") (pin "+") (pinfunction "+_+") (pintype "passive"))
      (node (ref "C13") (pin "P$2") (pinfunction "2_P$2") (pintype "passive"))
      (node (ref "C14") (pin "K") (pinfunction "-_K") (pintype "passive"))
      (node (ref "C15") (pin "P$2") (pinfunction "2_P$2") (pintype "passive"))
      (node (ref "C16") (pin "P$2") (pinfunction "2_P$2") (pintype "passive"))
      (node (ref "C17") (pin "P$2") (pinfunction "2_P$2") (pintype "passive"))
      (node (ref "C18") (pin "P$2") (pinfunction "2_P$2") (pintype "passive"))
      (node (ref "C19") (pin "P$2") (pinfunction "2_P$2") (pintype "passive"))
      (node (ref "C20") (pin "P$2") (pinfunction "2_P$2") (pintype "passive"))
      (node (ref "C21") (pin "P$2") (pinfunction "2_P$2") (pintype "passive"))
      (node (ref "C22") (pin "P$2") (pinfunction "2_P$2") (pintype "passive"))
      (node (ref "C24") (pin "P$2") (pinfunction "2_P$2") (pintype "passive"))
      (node (ref "C25") (pin "P$2") (pinfunction "2_P$2") (pintype "passive"))
      (node (ref "C26") (pin "P$2") (pinfunction "2_P$2") (pintype "passive"))
      (node (ref "C27") (pin "P$2") (pinfunction "2_P$2") (pintype "passive"))
      (node (ref "C28") (pin "P$2") (pinfunction "2_P$2") (pintype "passive"))
      (node (ref "C29") (pin "P$2") (pinfunction "2_P$2") (pintype "passive"))
      (node (ref "C30") (pin "P$2") (pinfunction "2_P$2") (pintype "passive"))
      (node (ref "C31") (pin "P$2") (pinfunction "2_P$2") (pintype "passive"))
      (node (ref "C32") (pin "P$2") (pinfunction "2_P$2") (pintype "passive"))
      (node (ref "C33") (pin "P$2") (pinfunction "2_P$2") (pintype "passive"))
      (node (ref "C34") (pin "P$2") (pinfunction "2_P$2") (pintype "passive"))
      (node (ref "C35") (pin "P$2") (pinfunction "2_P$2") (pintype "passive"))
      (node (ref "C36") (pin "P$2") (pinfunction "2_P$2") (pintype "passive"))
      (node (ref "C37") (pin "P$1") (pinfunction "1_P$1") (pintype "passive"))
      (node (ref "C38") (pin "P$2") (pinfunction "2_P$2") (pintype "passive"))
      (node (ref "C39") (pin "P$1") (pinfunction "1_P$1") (pintype "passive"))
      (node (ref "C40") (pin "P$2") (pinfunction "2_P$2") (pintype "passive"))
      (node (ref "C6") (pin "P$2") (pinfunction "2_P$2") (pintype "passive"))
      (node (ref "C7") (pin "P$1") (pinfunction "1_P$1") (pintype "passive"))
      (node (ref "C9") (pin "-") (pinfunction "-_-") (pintype "passive"))
      (node (ref "D15") (pin "A") (pinfunction "A_A") (pintype "bidirectional"))
      (node (ref "D16") (pin "K") (pinfunction "K_K") (pintype "passive"))
      (node (ref "D17") (pin "K") (pinfunction "K_K") (pintype "passive"))
      (node (ref "D5") (pin "K") (pinfunction "K_K") (pintype "passive"))
      (node (ref "J2") (pin "2") (pinfunction "2_2") (pintype "bidirectional"))
      (node (ref "J3") (pin "05") (pinfunction "05_05") (pintype "passive"))
      (node (ref "J3") (pin "07") (pinfunction "07_07") (pintype "passive"))
      (node (ref "J4") (pin "1") (pinfunction "SLEEVE_1") (pintype "passive"))
      (node (ref "J5") (pin "P$1") (pinfunction "1_P$1") (pintype "bidirectional"))
      (node (ref "J5") (pin "P$7") (pinfunction "SUP_P$7") (pintype "bidirectional"))
      (node (ref "J5") (pin "P$8") (pinfunction "SUP_P$8") (pintype "bidirectional"))
      (node (ref "J6") (pin "13") (pinfunction "13_13") (pintype "bidirectional"))
      (node (ref "J6") (pin "6") (pinfunction "6_6") (pintype "bidirectional"))
      (node (ref "PS1") (pin "-VOUT") (pinfunction "-VOUT_-VOUT") (pintype "passive"))
      (node (ref "PS2") (pin "+VOUT") (pinfunction "+VOUT_+VOUT") (pintype "passive"))
      (node (ref "R14") (pin "2") (pinfunction "2_2") (pintype "passive"))
      (node (ref "R19") (pin "P$1") (pinfunction "1_P$1") (pintype "passive"))
      (node (ref "R22") (pin "1") (pinfunction "1_1") (pintype "passive"))
      (node (ref "R26") (pin "1") (pinfunction "1_1") (pintype "passive"))
      (node (ref "R27") (pin "2") (pinfunction "2_2") (pintype "passive"))
      (node (ref "R32") (pin "3") (pinfunction "2_3") (pintype "passive"))
      (node (ref "R33") (pin "2") (pinfunction "2_2") (pintype "passive"))
      (node (ref "R34") (pin "2") (pinfunction "2_2") (pintype "passive"))
      (node (ref "R39") (pin "1") (pinfunction "1_1") (pintype "passive"))
      (node (ref "S1") (pin "P$3") (pinfunction "P$2_P$3") (pintype "bidirectional"))
      (node (ref "S1") (pin "P$4") (pinfunction "P$2_P$4") (pintype "bidirectional"))
      (node (ref "SHIELD1") (pin "P$1") (pinfunction "1_P$1") (pintype "bidirectional"))
      (node (ref "SHIELD1") (pin "P$2") (pinfunction "1_P$2") (pintype "bidirectional"))
      (node (ref "SJ5") (pin "NO") (pinfunction "NO_NO") (pintype "passive"))
      (node (ref "SW1") (pin "P$2") (pinfunction "P$2_P$2") (pintype "passive"))
      (node (ref "SW1") (pin "P$4") (pinfunction "P$4_P$4") (pintype "passive"))
      (node (ref "SW1") (pin "P$6") (pinfunction "P$6_P$6") (pintype "passive"))
      (node (ref "TP2") (pin "1") (pinfunction "P_1") (pintype "bidirectional"))
      (node (ref "U2") (pin "5") (pinfunction "GND2_5") (pintype "power_in"))
      (node (ref "U3") (pin "2") (pinfunction "GND_2") (pintype "power_in"))
      (node (ref "U4") (pin "2") (pinfunction "GND_2") (pintype "power_in"))
      (node (ref "U5") (pin "2") (pinfunction "GND_2") (pintype "power_in"))
      (node (ref "U6") (pin "23") (pinfunction "VSSD/VREFSD-_23") (pintype "input"))
      (node (ref "U6") (pin "47") (pinfunction "VSS_47") (pintype "power_in"))
      (node (ref "U6") (pin "8") (pinfunction "VSSA/VREF-_8") (pintype "input"))
      (node (ref "U7") (pin "12") (pinfunction "+IN_12") (pintype "input"))
      (node (ref "U7") (pin "5") (pinfunction "+IN_5") (pintype "input"))
    )
    (net (code "29") (name "GND-1") (class "Default")
      (node (ref "C1") (pin "P$2") (pinfunction "2_P$2") (pintype "passive"))
      (node (ref "C11") (pin "P$2") (pinfunction "2_P$2") (pintype "passive"))
      (node (ref "C12") (pin "P$2") (pinfunction "2_P$2") (pintype "passive"))
      (node (ref "C2") (pin "P$2") (pinfunction "2_P$2") (pintype "passive"))
      (node (ref "C3") (pin "P$2") (pinfunction "2_P$2") (pintype "passive"))
      (node (ref "C4") (pin "P$2") (pinfunction "2_P$2") (pintype "passive"))
      (node (ref "C5") (pin "P$2") (pinfunction "2_P$2") (pintype "passive"))
      (node (ref "C8") (pin "P$2") (pinfunction "2_P$2") (pintype "passive"))
      (node (ref "D1") (pin "C") (pinfunction "P$2_C") (pintype "bidirectional"))
      (node (ref "D2") (pin "C") (pinfunction "P$2_C") (pintype "bidirectional"))
      (node (ref "D3") (pin "C") (pinfunction "P$2_C") (pintype "bidirectional"))
      (node (ref "J1") (pin "4") (pinfunction "GND_4") (pintype "power_in"))
      (node (ref "PS1") (pin "-VIN") (pinfunction "-VIN_-VIN") (pintype "passive"))
      (node (ref "PS2") (pin "-VIN") (pinfunction "-VIN_-VIN") (pintype "passive"))
      (node (ref "R1") (pin "2") (pinfunction "2_2") (pintype "passive"))
      (node (ref "R3") (pin "2") (pinfunction "2_2") (pintype "passive"))
      (node (ref "U1") (pin "3") (pinfunction "GND_3") (pintype "power_in"))
      (node (ref "U1") (pin "EXP") (pinfunction "GND_EXP") (pintype "power_in"))
      (node (ref "U2") (pin "4") (pinfunction "GND1_4") (pintype "power_in"))
    )
    (net (code "30") (name "I_ABC") (class "Default")
      (node (ref "Q1") (pin "3") (pinfunction "C_3") (pintype "passive"))
      (node (ref "U8") (pin "1") (pinfunction "AMP_BIAS_1") (pintype "bidirectional"))
    )
    (net (code "31") (name "JCLK") (class "Default")
      (node (ref "J2") (pin "3") (pinfunction "3_3") (pintype "bidirectional"))
      (node (ref "J3") (pin "06") (pinfunction "06_06") (pintype "passive"))
      (node (ref "SJ4") (pin "2") (pinfunction "2_2") (pintype "passive"))
      (node (ref "U6") (pin "37") (pinfunction "PA14_37") (pintype "bidirectional"))
    )
    (net (code "32") (name "JRCLK") (class "Default")
      (node (ref "J3") (pin "09") (pinfunction "09_09") (pintype "passive"))
      (node (ref "SJ4") (pin "1") (pinfunction "1_1") (pintype "passive"))
    )
    (net (code "33") (name "JTDI") (class "Default")
      (node (ref "J3") (pin "10") (pinfunction "10_10") (pintype "passive"))
      (node (ref "U6") (pin "38") (pinfunction "PA15_38") (pintype "bidirectional"))
    )
    (net (code "34") (name "JTDO") (class "Default")
      (node (ref "J3") (pin "08") (pinfunction "08_08") (pintype "passive"))
      (node (ref "U6") (pin "39") (pinfunction "PB3_39") (pintype "bidirectional"))
    )
    (net (code "35") (name "JTMS") (class "Default")
      (node (ref "J2") (pin "1") (pinfunction "1_1") (pintype "bidirectional"))
      (node (ref "J3") (pin "04") (pinfunction "04_04") (pintype "passive"))
      (node (ref "U6") (pin "34") (pinfunction "PA13_34") (pintype "bidirectional"))
    )
    (net (code "36") (name "MCU_RX") (class "Default")
      (node (ref "J3") (pin "13") (pinfunction "13_13") (pintype "passive"))
      (node (ref "R15") (pin "2") (pinfunction "2_2") (pintype "passive"))
    )
    (net (code "37") (name "MCU_TX") (class "Default")
      (node (ref "J3") (pin "14") (pinfunction "14_14") (pintype "passive"))
      (node (ref "R16") (pin "2") (pinfunction "2_2") (pintype "passive"))
    )
    (net (code "38") (name "NRST") (class "Default")
      (node (ref "C23") (pin "P$2") (pinfunction "2_P$2") (pintype "passive"))
      (node (ref "J3") (pin "12") (pinfunction "12_12") (pintype "passive"))
      (node (ref "R9") (pin "1") (pinfunction "1_1") (pintype "passive"))
      (node (ref "S1") (pin "P$1") (pinfunction "P$1_P$1") (pintype "bidirectional"))
      (node (ref "S1") (pin "P$2") (pinfunction "P$1_P$2") (pintype "bidirectional"))
      (node (ref "U6") (pin "7") (pinfunction "NRST_7") (pintype "input"))
    )
    (net (code "39") (name "Net-(C3-1)") (class "Default")
      (node (ref "C3") (pin "P$1") (pinfunction "1_P$1") (pintype "passive"))
      (node (ref "J1") (pin "M1") (pinfunction "SHIELD_M1") (pintype "power_in"))
      (node (ref "J1") (pin "M2") (pinfunction "SHIELD_M2") (pintype "power_in"))
      (node (ref "R1") (pin "1") (pinfunction "1_1") (pintype "passive"))
    )
    (net (code "40") (name "Net-(C16-1)") (class "Default")
      (node (ref "C16") (pin "P$1") (pinfunction "1_P$1") (pintype "passive"))
      (node (ref "R7") (pin "1") (pinfunction "1_1") (pintype "passive"))
      (node (ref "U3") (pin "3") (pinfunction "EN_3") (pintype "input"))
    )
    (net (code "41") (name "Net-(C17-1)") (class "Default")
      (node (ref "C17") (pin "P$1") (pinfunction "1_P$1") (pintype "passive"))
      (node (ref "C18") (pin "P$1") (pinfunction "1_P$1") (pintype "passive"))
      (node (ref "SJ1") (pin "2") (pinfunction "2_2") (pintype "passive"))
      (node (ref "TP3") (pin "1") (pinfunction "P_1") (pintype "bidirectional"))
      (node (ref "U3") (pin "5") (pinfunction "OUT_5") (pintype "power_in"))
    )
    (net (code "42") (name "Net-(C20-1)") (class "Default")
      (node (ref "C20") (pin "P$1") (pinfunction "1_P$1") (pintype "passive"))
      (node (ref "C21") (pin "P$1") (pinfunction "1_P$1") (pintype "passive"))
      (node (ref "SJ2") (pin "2") (pinfunction "2_2") (pintype "passive"))
      (node (ref "U4") (pin "5") (pinfunction "OUT_5") (pintype "power_in"))
    )
    (net (code "43") (name "Net-(C40-1)") (class "Default")
      (node (ref "C40") (pin "P$1") (pinfunction "1_P$1") (pintype "passive"))
      (node (ref "R21") (pin "1") (pinfunction "1_1") (pintype "passive"))
      (node (ref "R22") (pin "2") (pinfunction "2_2") (pintype "passive"))
      (node (ref "U7") (pin "3") (pinfunction "+IN_3") (pintype "input"))
    )
    (net (code "44") (name "Net-(C41-1)") (class "Default")
      (node (ref "C41") (pin "P$1") (pinfunction "1_P$1") (pintype "passive"))
      (node (ref "R20") (pin "1") (pinfunction "1_1") (pintype "passive"))
      (node (ref "R23") (pin "2") (pinfunction "2_2") (pintype "passive"))
      (node (ref "U7") (pin "2") (pinfunction "-IN_2") (pintype "input"))
    )
    (net (code "45") (name "Net-(C42-1)") (class "Default")
      (node (ref "C42") (pin "P$1") (pinfunction "1_P$1") (pintype "passive"))
      (node (ref "C43") (pin "1") (pinfunction "+_1") (pintype "passive"))
      (node (ref "R24") (pin "2") (pinfunction "2_2") (pintype "passive"))
      (node (ref "SJ7") (pin "P$1") (pinfunction "P$1_P$1") (pintype "bidirectional"))
      (node (ref "TP5") (pin "TP") (pinfunction "TP_TP") (pintype "input"))
      (node (ref "U7") (pin "14") (pinfunction "OUT_14") (pintype "output"))
    )
    (net (code "46") (name "Net-(C43--)") (class "Default")
      (node (ref "C43") (pin "2") (pinfunction "-_2") (pintype "passive"))
      (node (ref "R35") (pin "1") (pinfunction "1_1") (pintype "passive"))
      (node (ref "SJ7") (pin "P$2") (pinfunction "P$2_P$2") (pintype "bidirectional"))
    )
    (net (code "47") (name "Net-(D2-P$1)") (class "Default")
      (node (ref "D2") (pin "A") (pinfunction "P$1_A") (pintype "bidirectional"))
      (node (ref "J1") (pin "3") (pinfunction "D+_3") (pintype "bidirectional"))
      (node (ref "U1") (pin "4") (pinfunction "D+_4") (pintype "bidirectional"))
    )
    (net (code "48") (name "Net-(D3-P$1)") (class "Default")
      (node (ref "D3") (pin "A") (pinfunction "P$1_A") (pintype "bidirectional"))
      (node (ref "J1") (pin "2") (pinfunction "D-_2") (pintype "bidirectional"))
      (node (ref "U1") (pin "5") (pinfunction "D-_5") (pintype "bidirectional"))
    )
    (net (code "49") (name "Net-(D5-PadA)") (class "Default")
      (node (ref "D5") (pin "A") (pinfunction "A_A") (pintype "passive"))
      (node (ref "R12") (pin "2") (pinfunction "2_2") (pintype "passive"))
    )
    (net (code "50") (name "Net-(D7-K)") (class "Default")
      (node (ref "D6") (pin "A") (pinfunction "A_A") (pintype "bidirectional"))
      (node (ref "D7") (pin "C") (pinfunction "K_C") (pintype "bidirectional"))
      (node (ref "D8") (pin "A") (pinfunction "A_A") (pintype "bidirectional"))
      (node (ref "D9") (pin "C") (pinfunction "K_C") (pintype "bidirectional"))
      (node (ref "R21") (pin "2") (pinfunction "2_2") (pintype "passive"))
      (node (ref "SJ5") (pin "NC") (pinfunction "NC_NC") (pintype "passive"))
    )
    (net (code "51") (name "Net-(D11-K)") (class "Default")
      (node (ref "D10") (pin "A") (pinfunction "A_A") (pintype "bidirectional"))
      (node (ref "D11") (pin "C") (pinfunction "K_C") (pintype "bidirectional"))
      (node (ref "D8") (pin "C") (pinfunction "K_C") (pintype "bidirectional"))
      (node (ref "D9") (pin "A") (pinfunction "A_A") (pintype "bidirectional"))
      (node (ref "J4") (pin "2") (pinfunction "TIP_2") (pintype "passive"))
      (node (ref "R20") (pin "2") (pinfunction "2_2") (pintype "passive"))
    )
    (net (code "52") (name "Net-(D12-K)") (class "Default")
      (node (ref "D12") (pin "C") (pinfunction "K_C") (pintype "bidirectional"))
      (node (ref "D13") (pin "A") (pinfunction "A_A") (pintype "bidirectional"))
    )
    (net (code "53") (name "Net-(D13-K)") (class "Default")
      (node (ref "D13") (pin "C") (pinfunction "K_C") (pintype "bidirectional"))
      (node (ref "Q2") (pin "1") (pinfunction "B_1") (pintype "passive"))
      (node (ref "R26") (pin "2") (pinfunction "2_2") (pintype "passive"))
    )
    (net (code "54") (name "Net-(D16-PadA)") (class "Default")
      (node (ref "D16") (pin "A") (pinfunction "A_A") (pintype "passive"))
      (node (ref "R37") (pin "2") (pinfunction "2_2") (pintype "passive"))
    )
    (net (code "55") (name "Net-(D17-PadA)") (class "Default")
      (node (ref "D17") (pin "A") (pinfunction "A_A") (pintype "passive"))
      (node (ref "R38") (pin "2") (pinfunction "2_2") (pintype "passive"))
    )
    (net (code "56") (name "Net-(J4-RING)") (class "Default")
      (node (ref "J4") (pin "3") (pinfunction "RING_3") (pintype "passive"))
      (node (ref "SJ5") (pin "COM") (pinfunction "COM_COM") (pintype "passive"))
    )
    (net (code "57") (name "Net-(J5-2)") (class "Default")
      (node (ref "J5") (pin "P$2") (pinfunction "2_P$2") (pintype "bidirectional"))
      (node (ref "SJ6") (pin "COM") (pinfunction "COM_COM") (pintype "passive"))
    )
    (net (code "58") (name "Net-(Q1-B)") (class "Default")
      (node (ref "Q1") (pin "1") (pinfunction "B_1") (pintype "passive"))
      (node (ref "U7") (pin "7") (pinfunction "OUT_7") (pintype "output"))
    )
    (net (code "59") (name "Net-(Q1-E)") (class "Default")
      (node (ref "Q1") (pin "2") (pinfunction "E_2") (pintype "passive"))
      (node (ref "R17") (pin "1") (pinfunction "1_1") (pintype "passive"))
      (node (ref "R18") (pin "1") (pinfunction "1_1") (pintype "passive"))
      (node (ref "U7") (pin "6") (pinfunction "-IN_6") (pintype "input"))
    )
    (net (code "60") (name "Net-(Q2-C)") (class "Default")
      (node (ref "Q2") (pin "3") (pinfunction "C_3") (pintype "passive"))
      (node (ref "U8") (pin "2") (pinfunction "D_BIAS_2") (pintype "bidirectional"))
    )
    (net (code "61") (name "Net-(Q2-E)") (class "Default")
      (node (ref "Q2") (pin "2") (pinfunction "E_2") (pintype "passive"))
      (node (ref "R28") (pin "1") (pinfunction "1_1") (pintype "passive"))
    )
    (net (code "62") (name "Net-(R29-Pad1)") (class "Default")
      (node (ref "R29") (pin "1") (pinfunction "1_1") (pintype "passive"))
      (node (ref "R30") (pin "1") (pinfunction "1_1") (pintype "passive"))
    )
    (net (code "63") (name "Net-(R29-Pad2)") (class "Default")
      (node (ref "R29") (pin "2") (pinfunction "2_2") (pintype "passive"))
      (node (ref "R33") (pin "1") (pinfunction "1_1") (pintype "passive"))
      (node (ref "R34") (pin "1") (pinfunction "1_1") (pintype "passive"))
    )
    (net (code "64") (name "Net-(R30-2)") (class "Default")
      (node (ref "R30") (pin "2") (pinfunction "C_2") (pintype "bidirectional"))
      (node (ref "R30") (pin "3") (pinfunction "2_3") (pintype "passive"))
      (node (ref "U8") (pin "4") (pinfunction "-_4") (pintype "bidirectional"))
    )
    (net (code "65") (name "Net-(R31-Pad1)") (class "Default")
      (node (ref "R31") (pin "1") (pinfunction "1_1") (pintype "passive"))
      (node (ref "R32") (pin "1") (pinfunction "1_1") (pintype "passive"))
    )
    (net (code "66") (name "Net-(R32-C)") (class "Default")
      (node (ref "R32") (pin "2") (pinfunction "C_2") (pintype "bidirectional"))
      (node (ref "U7") (pin "10") (pinfunction "+IN_10") (pintype "input"))
    )
    (net (code "67") (name "Net-(U1-~{RST})") (class "Default")
      (node (ref "R4") (pin "2") (pinfunction "2_2") (pintype "passive"))
      (node (ref "U1") (pin "9") (pinfunction "~{RST}_9") (pintype "bidirectional"))
    )
    (net (code "68") (name "Net-(U7C--IN)") (class "Default")
      (node (ref "R35") (pin "2") (pinfunction "2_2") (pintype "passive"))
      (node (ref "R36") (pin "1") (pinfunction "1_1") (pintype "passive"))
      (node (ref "U7") (pin "9") (pinfunction "-IN_9") (pintype "input"))
    )
    (net (code "69") (name "Net-(U8A-+)") (class "Default")
      (node (ref "R25") (pin "2") (pinfunction "2_2") (pintype "passive"))
      (node (ref "R27") (pin "1") (pinfunction "1_1") (pintype "passive"))
      (node (ref "U8") (pin "3") (pinfunction "+_3") (pintype "bidirectional"))
    )
    (net (code "70") (name "OSC2_IN") (class "Default")
      (node (ref "C25") (pin "P$1") (pinfunction "1_P$1") (pintype "passive"))
      (node (ref "U6") (pin "5") (pinfunction "PF0/OSC_IN_5") (pintype "bidirectional"))
      (node (ref "XTAL1") (pin "P$3") (pinfunction "X2_P$3") (pintype "passive"))
    )
    (net (code "71") (name "OSC2_OUT") (class "Default")
      (node (ref "C27") (pin "P$1") (pinfunction "1_P$1") (pintype "passive"))
      (node (ref "U6") (pin "6") (pinfunction "PF1/OSC_OUT_6") (pintype "bidirectional"))
      (node (ref "XTAL1") (pin "P$1") (pinfunction "X1_P$1") (pintype "passive"))
    )
    (net (code "72") (name "OUT_CHARGE_AMP") (class "Default")
      (node (ref "C41") (pin "P$2") (pinfunction "2_P$2") (pintype "passive"))
      (node (ref "R23") (pin "1") (pinfunction "1_1") (pintype "passive"))
      (node (ref "R25") (pin "1") (pinfunction "1_1") (pintype "passive"))
      (node (ref "TP8") (pin "TP") (pinfunction "TP_TP") (pintype "input"))
      (node (ref "U7") (pin "1") (pinfunction "OUT_1") (pintype "output"))
    )
    (net (code "73") (name "OUT_OTA") (class "Default")
      (node (ref "C42") (pin "P$2") (pinfunction "2_P$2") (pintype "passive"))
      (node (ref "R24") (pin "1") (pinfunction "1_1") (pintype "passive"))
      (node (ref "U7") (pin "13") (pinfunction "-IN_13") (pintype "input"))
      (node (ref "U8") (pin "5") (pinfunction "OUT_5") (pintype "bidirectional"))
    )
    (net (code "74") (name "POWER_LED") (class "Default")
      (node (ref "J5") (pin "P$5") (pinfunction "5_P$5") (pintype "bidirectional"))
      (node (ref "U6") (pin "43") (pinfunction "PB7_43") (pintype "bidirectional"))
    )
    (net (code "75") (name "RXD") (class "Default")
      (node (ref "U1") (pin "25") (pinfunction "RXD_25") (pintype "input"))
      (node (ref "U2") (pin "2") (pinfunction "OUT_A_2") (pintype "output"))
    )
    (net (code "76") (name "SDADC1_CH4") (class "Default")
      (node (ref "J6") (pin "3") (pinfunction "3_3") (pintype "bidirectional"))
      (node (ref "U6") (pin "20") (pinfunction "PB2_20") (pintype "bidirectional"))
    )
    (net (code "77") (name "SDADC1_CH5") (class "Default")
      (node (ref "D14") (pin "A") (pinfunction "A_A") (pintype "bidirectional"))
      (node (ref "D15") (pin "C") (pinfunction "K_C") (pintype "bidirectional"))
      (node (ref "R36") (pin "2") (pinfunction "2_2") (pintype "passive"))
      (node (ref "TP6") (pin "TP") (pinfunction "TP_TP") (pintype "input"))
      (node (ref "U6") (pin "19") (pinfunction "PB1_19") (pintype "bidirectional"))
      (node (ref "U7") (pin "8") (pinfunction "OUT_8") (pintype "output"))
    )
    (net (code "78") (name "SDADC1_CH6") (class "Default")
      (node (ref "R19") (pin "P$2") (pinfunction "C_P$2") (pintype "bidirectional"))
      (node (ref "TP10") (pin "TP") (pinfunction "TP_TP") (pintype "input"))
      (node (ref "U6") (pin "18") (pinfunction "PB0_18") (pintype "bidirectional"))
    )
    (net (code "79") (name "SDADC1_CH7") (class "Default")
      (node (ref "TP9") (pin "TP") (pinfunction "TP_TP") (pintype "input"))
      (node (ref "U6") (pin "22") (pinfunction "PE9_22") (pintype "bidirectional"))
    )
    (net (code "80") (name "SDADC1_CH8") (class "Default")
      (node (ref "J6") (pin "4") (pinfunction "4_4") (pintype "bidirectional"))
      (node (ref "U6") (pin "21") (pinfunction "PE8_21") (pintype "bidirectional"))
    )
    (net (code "81") (name "SDADC3_CH7") (class "Default")
      (node (ref "J6") (pin "10") (pinfunction "10_10") (pintype "bidirectional"))
      (node (ref "U6") (pin "27") (pinfunction "PB15_27") (pintype "bidirectional"))
    )
    (net (code "82") (name "SDADC3_CH8") (class "Default")
      (node (ref "J6") (pin "11") (pinfunction "11_11") (pintype "bidirectional"))
      (node (ref "U6") (pin "26") (pinfunction "PB14_26") (pintype "bidirectional"))
    )
    (net (code "83") (name "SW_1") (class "Default")
      (node (ref "R10") (pin "1") (pinfunction "1_1") (pintype "passive"))
      (node (ref "SW1") (pin "P$1") (pinfunction "P$1_P$1") (pintype "passive"))
      (node (ref "U6") (pin "2") (pinfunction "PC13_2") (pintype "bidirectional"))
    )
    (net (code "84") (name "SW_2") (class "Default")
      (node (ref "R11") (pin "1") (pinfunction "1_1") (pintype "passive"))
      (node (ref "SW1") (pin "P$3") (pinfunction "P$3_P$3") (pintype "passive"))
      (node (ref "U6") (pin "3") (pinfunction "PC14/OSC32_IN_3") (pintype "bidirectional"))
    )
    (net (code "85") (name "SW_3") (class "Default")
      (node (ref "R13") (pin "1") (pinfunction "1_1") (pintype "passive"))
      (node (ref "SW1") (pin "P$5") (pinfunction "P$5_P$5") (pintype "passive"))
      (node (ref "U6") (pin "4") (pinfunction "PC15/OSC32_OUT_4") (pintype "bidirectional"))
    )
    (net (code "86") (name "TXD") (class "Default")
      (node (ref "U1") (pin "26") (pinfunction "TXD_26") (pintype "output"))
      (node (ref "U2") (pin "3") (pinfunction "IN_B_3") (pintype "input"))
    )
    (net (code "87") (name "USART_RX") (class "Default")
      (node (ref "R15") (pin "1") (pinfunction "1_1") (pintype "passive"))
      (node (ref "R6") (pin "2") (pinfunction "2_2") (pintype "passive"))
      (node (ref "U6") (pin "31") (pinfunction "PA10_31") (pintype "bidirectional"))
    )
    (net (code "88") (name "USART_TX") (class "Default")
      (node (ref "R16") (pin "1") (pinfunction "1_1") (pintype "passive"))
      (node (ref "R5") (pin "2") (pinfunction "2_2") (pintype "passive"))
      (node (ref "U6") (pin "30") (pinfunction "PA9_30") (pintype "bidirectional"))
    )
    (net (code "89") (name "USB_DET") (class "Default")
      (node (ref "R2") (pin "1") (pinfunction "1_1") (pintype "passive"))
      (node (ref "R3") (pin "1") (pinfunction "1_1") (pintype "passive"))
      (node (ref "U1") (pin "8") (pinfunction "VBUS_8") (pintype "input"))
    )
    (net (code "90") (name "USB_RXD") (class "Default")
      (node (ref "R5") (pin "1") (pinfunction "1_1") (pintype "passive"))
      (node (ref "U2") (pin "7") (pinfunction "INA_A_7") (pintype "input"))
    )
    (net (code "91") (name "USB_TXD") (class "Default")
      (node (ref "R6") (pin "1") (pinfunction "1_1") (pintype "passive"))
      (node (ref "U2") (pin "6") (pinfunction "OUT_B_6") (pintype "output"))
    )
    (net (code "92") (name "VBAT") (class "Default")
      (node (ref "U6") (pin "1") (pinfunction "VBAT_1") (pintype "power_in"))
    )
    (net (code "93") (name "VDD_BRIDGE") (class "Default")
      (node (ref "C11") (pin "P$1") (pinfunction "1_P$1") (pintype "passive"))
      (node (ref "C8") (pin "P$1") (pinfunction "1_P$1") (pintype "passive"))
      (node (ref "R4") (pin "1") (pinfunction "1_1") (pintype "passive"))
      (node (ref "U1") (pin "6") (pinfunction "VDD_6") (pintype "power_in"))
    )
    (net (code "94") (name "VREF_SDADC") (class "Default")
      (node (ref "C34") (pin "P$1") (pinfunction "1_P$1") (pintype "passive"))
      (node (ref "C35") (pin "P$1") (pinfunction "1_P$1") (pintype "passive"))
      (node (ref "SJ3") (pin "2") (pinfunction "2_2") (pintype "passive"))
      (node (ref "U6") (pin "25") (pinfunction "VREFSD+_25") (pintype "input"))
    )
    (net (code "95") (name "VUSB") (class "Default")
      (node (ref "C1") (pin "P$1") (pinfunction "1_P$1") (pintype "passive"))
      (node (ref "C12") (pin "P$1") (pinfunction "1_P$1") (pintype "passive"))
      (node (ref "C2") (pin "P$1") (pinfunction "1_P$1") (pintype "passive"))
      (node (ref "C4") (pin "P$1") (pinfunction "1_P$1") (pintype "passive"))
      (node (ref "C5") (pin "P$1") (pinfunction "1_P$1") (pintype "passive"))
      (node (ref "D1") (pin "A") (pinfunction "P$1_A") (pintype "bidirectional"))
      (node (ref "J1") (pin "1") (pinfunction "VCC_1") (pintype "power_in"))
      (node (ref "PS1") (pin "+VIN") (pinfunction "+VIN_+VIN") (pintype "passive"))
      (node (ref "PS2") (pin "+VIN") (pinfunction "+VIN_+VIN") (pintype "passive"))
      (node (ref "R2") (pin "2") (pinfunction "2_2") (pintype "passive"))
      (node (ref "U1") (pin "7") (pinfunction "REGIN_7") (pintype "power_in"))
      (node (ref "U2") (pin "1") (pinfunction "VCC1_1") (pintype "power_in"))
    )
    (net (code "96") (name "unconnected-(J3-Pad01)") (class "Default")
      (node (ref "J3") (pin "01") (pinfunction "01_01") (pintype "passive"))
    )
    (net (code "97") (name "unconnected-(J3-Pad02)") (class "Default")
      (node (ref "J3") (pin "02") (pinfunction "02_02") (pintype "passive"))
    )
    (net (code "98") (name "unconnected-(J3-Pad11)") (class "Default")
      (node (ref "J3") (pin "11") (pinfunction "11_11") (pintype "passive"))
    )
    (net (code "99") (name "unconnected-(U1-CHR0-Pad15)") (class "Default")
      (node (ref "U1") (pin "15") (pinfunction "CHR0_15") (pintype "output"))
    )
    (net (code "100") (name "unconnected-(U1-CHR1-Pad14)") (class "Default")
      (node (ref "U1") (pin "14") (pinfunction "CHR1_14") (pintype "output"))
    )
    (net (code "101") (name "unconnected-(U1-CHREN-Pad13)") (class "Default")
      (node (ref "U1") (pin "13") (pinfunction "CHREN_13") (pintype "output"))
    )
    (net (code "102") (name "unconnected-(U1-CTS-Pad23)") (class "Default")
      (node (ref "U1") (pin "23") (pinfunction "CTS_23") (pintype "input"))
    )
    (net (code "103") (name "unconnected-(U1-DCD-Pad1)") (class "Default")
      (node (ref "U1") (pin "1") (pinfunction "DCD_1") (pintype "input"))
    )
    (net (code "104") (name "unconnected-(U1-DSR-Pad27)") (class "Default")
      (node (ref "U1") (pin "27") (pinfunction "DSR_27") (pintype "input"))
    )
    (net (code "105") (name "unconnected-(U1-DTR-Pad28)") (class "Default")
      (node (ref "U1") (pin "28") (pinfunction "DTR_28") (pintype "output"))
    )
    (net (code "106") (name "unconnected-(U1-GPIO0{slash}TXT-Pad19)") (class "Default")
      (node (ref "U1") (pin "19") (pinfunction "GPIO0/TXT_19") (pintype "bidirectional"))
    )
    (net (code "107") (name "unconnected-(U1-GPIO1{slash}RXT-Pad18)") (class "Default")
      (node (ref "U1") (pin "18") (pinfunction "GPIO1/RXT_18") (pintype "bidirectional"))
    )
    (net (code "108") (name "unconnected-(U1-GPIO2{slash}RS485-Pad17)") (class "Default")
      (node (ref "U1") (pin "17") (pinfunction "GPIO2/RS485_17") (pintype "bidirectional"))
    )
    (net (code "109") (name "unconnected-(U1-GPIO3{slash}WAKEUP-Pad16)") (class "Default")
      (node (ref "U1") (pin "16") (pinfunction "GPIO3/WAKEUP_16") (pintype "bidirectional"))
    )
    (net (code "110") (name "unconnected-(U1-GPIO4-Pad22)") (class "Default")
      (node (ref "U1") (pin "22") (pinfunction "GPIO4_22") (pintype "bidirectional"))
    )
    (net (code "111") (name "unconnected-(U1-GPIO5-Pad21)") (class "Default")
      (node (ref "U1") (pin "21") (pinfunction "GPIO5_21") (pintype "bidirectional"))
    )
    (net (code "112") (name "unconnected-(U1-GPIO6-Pad20)") (class "Default")
      (node (ref "U1") (pin "20") (pinfunction "GPIO6_20") (pintype "bidirectional"))
    )
    (net (code "113") (name "unconnected-(U1-RI-Pad2)") (class "Default")
      (node (ref "U1") (pin "2") (pinfunction "RI_2") (pintype "bidirectional"))
    )
    (net (code "114") (name "unconnected-(U1-RTS-Pad24)") (class "Default")
      (node (ref "U1") (pin "24") (pinfunction "RTS_24") (pintype "output"))
    )
    (net (code "115") (name "unconnected-(U1-SUSPEND-Pad12)") (class "Default")
      (node (ref "U1") (pin "12") (pinfunction "SUSPEND_12") (pintype "output"))
    )
    (net (code "116") (name "unconnected-(U1-~{SUSPEND}-Pad11)") (class "Default")
      (node (ref "U1") (pin "11") (pinfunction "~{SUSPEND}_11") (pintype "output"))
    )
    (net (code "117") (name "unconnected-(U3-N{slash}C-Pad4)") (class "Default")
      (node (ref "U3") (pin "4") (pinfunction "N/C_4") (pintype "no_connect"))
    )
    (net (code "118") (name "unconnected-(U4-N{slash}C-Pad4)") (class "Default")
      (node (ref "U4") (pin "4") (pinfunction "N/C_4") (pintype "no_connect"))
    )
    (net (code "119") (name "unconnected-(U6-PA0-Pad10)") (class "Default")
      (node (ref "U6") (pin "10") (pinfunction "PA0_10") (pintype "bidirectional"))
    )
    (net (code "120") (name "unconnected-(U6-PA1-Pad11)") (class "Default")
      (node (ref "U6") (pin "11") (pinfunction "PA1_11") (pintype "bidirectional"))
    )
    (net (code "121") (name "unconnected-(U6-PA2-Pad12)") (class "Default")
      (node (ref "U6") (pin "12") (pinfunction "PA2_12") (pintype "bidirectional"))
    )
    (net (code "122") (name "unconnected-(U6-PA6-Pad16)") (class "Default")
      (node (ref "U6") (pin "16") (pinfunction "PA6_16") (pintype "bidirectional"))
    )
    (net (code "123") (name "unconnected-(U6-PA8-Pad29)") (class "Default")
      (node (ref "U6") (pin "29") (pinfunction "PA8_29") (pintype "bidirectional"))
    )
    (net (code "124") (name "unconnected-(U6-PA11-Pad32)") (class "Default")
      (node (ref "U6") (pin "32") (pinfunction "PA11_32") (pintype "bidirectional"))
    )
    (net (code "125") (name "unconnected-(U6-PA12-Pad33)") (class "Default")
      (node (ref "U6") (pin "33") (pinfunction "PA12_33") (pintype "bidirectional"))
    )
    (net (code "126") (name "unconnected-(U6-PB4-Pad40)") (class "Default")
      (node (ref "U6") (pin "40") (pinfunction "PB4_40") (pintype "bidirectional"))
    )
    (net (code "127") (name "unconnected-(U6-PB5-Pad41)") (class "Default")
      (node (ref "U6") (pin "41") (pinfunction "PB5_41") (pintype "bidirectional"))
    )
    (net (code "128") (name "unconnected-(U6-PD8-Pad28)") (class "Default")
      (node (ref "U6") (pin "28") (pinfunction "PD8_28") (pintype "bidirectional"))
    )
    (net (code "129") (name "unconnected-(U6-PF6-Pad35)") (class "Default")
      (node (ref "U6") (pin "35") (pinfunction "PF6_35") (pintype "bidirectional"))
    )
    (net (code "130") (name "unconnected-(U6-PF7-Pad36)") (class "Default")
      (node (ref "U6") (pin "36") (pinfunction "PF7_36") (pintype "bidirectional"))
    )
    (net (code "131") (name "unconnected-(U8A-B-Pad7)") (class "Default")
      (node (ref "U8") (pin "7") (pinfunction "B_7") (pintype "passive"))
    )
    (net (code "132") (name "unconnected-(U8A-E-Pad8)") (class "Default")
      (node (ref "U8") (pin "8") (pinfunction "E_8") (pintype "passive"))
    )
    (net (code "133") (name "unconnected-(U8B-+-Pad14)") (class "Default")
      (node (ref "U8") (pin "14") (pinfunction "+_14") (pintype "bidirectional"))
    )
    (net (code "134") (name "unconnected-(U8B---Pad13)") (class "Default")
      (node (ref "U8") (pin "13") (pinfunction "-_13") (pintype "bidirectional"))
    )
    (net (code "135") (name "unconnected-(U8B-B-Pad10)") (class "Default")
      (node (ref "U8") (pin "10") (pinfunction "B_10") (pintype "passive"))
    )
    (net (code "136") (name "unconnected-(U8B-D_BIAS-Pad15)") (class "Default")
      (node (ref "U8") (pin "15") (pinfunction "D_BIAS_15") (pintype "bidirectional"))
    )
    (net (code "137") (name "unconnected-(U8B-E-Pad9)") (class "Default")
      (node (ref "U8") (pin "9") (pinfunction "E_9") (pintype "passive"))
    )
    (net (code "138") (name "unconnected-(U8B-OUT-Pad12)") (class "Default")
      (node (ref "U8") (pin "12") (pinfunction "OUT_12") (pintype "bidirectional"))
    )
  )
)
